# ProPrj___2026-07-14.net
KiCad netlist of a schematic drawn in EasyEDA Pro
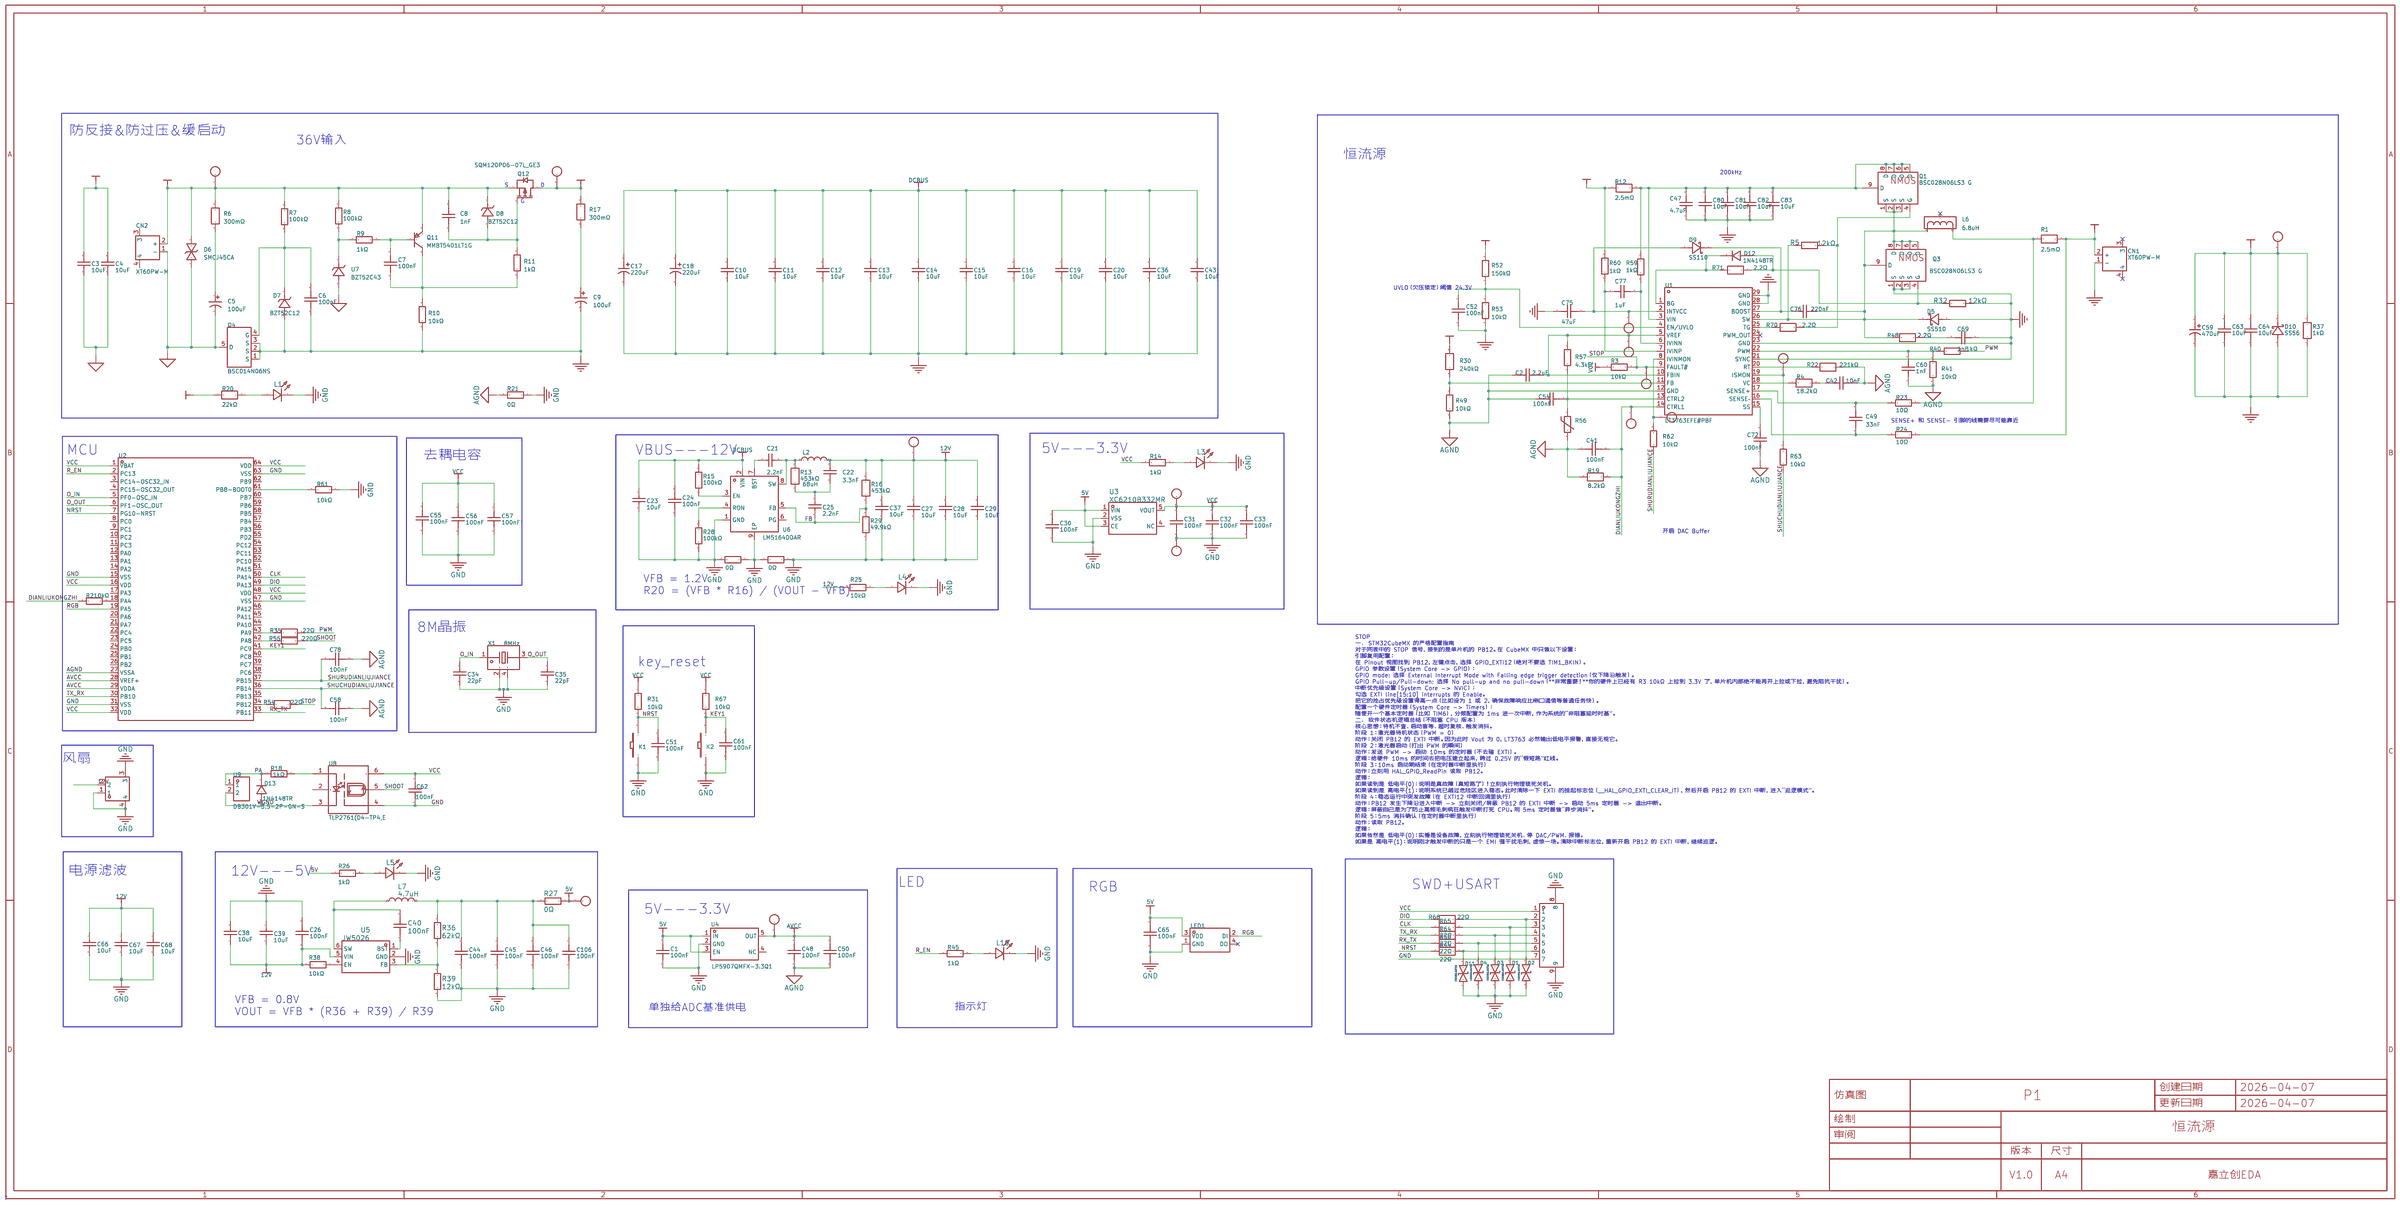
[diagram p0: schematic sheet]

(export (version "E")
  (design (tool "Eeschema 10.0.6"))
  (components
    (comp (ref "C1")
      (value "100nF")
      (description "容值:100nF;精度:±10%;额定电压:50V;温度系数:X7R;")
      (fields
        (field (name "Manufacturer Part") "CC0603KRX7R9BB104")
        (field (name "Manufacturer") "YAGEO(国巨)")
      )
      (libsource (lib "easyedapro") (part "CC0603KRX7R9BB104"))
    )
    (comp (ref "C2")
      (value "2.2uF")
      (footprint "easyedapro:C0603")
      (description "容值:2.2uF;精度:±10%;额定电压:25V;温度系数:X5R;")
      (fields
        (field (name "Manufacturer Part") "CL10A225KA8NNNC")
        (field (name "Manufacturer") "SAMSUNG(三星)")
      )
      (libsource (lib "easyedapro") (part "CL10A225KA8NNNC"))
    )
    (comp (ref "C3")
      (value "10uF")
      (footprint "easyedapro:C1210")
      (description "容值:10uF;精度:±10%;额定电压:50V;温度系数:X7R;")
      (fields
        (field (name "Manufacturer Part") "GRM32ER71H106KA12L")
        (field (name "Manufacturer") "muRata(村田)")
      )
      (libsource (lib "easyedapro") (part "GRM32ER71H106KA12L"))
    )
    (comp (ref "C4")
      (value "10uF")
      (footprint "easyedapro:C1210")
      (description "容值:10uF;精度:±10%;额定电压:50V;温度系数:X7R;")
      (fields
        (field (name "Manufacturer Part") "GRM32ER71H106KA12L")
        (field (name "Manufacturer") "muRata(村田)")
      )
      (libsource (lib "easyedapro") (part "GRM32ER71H106KA12L"))
    )
    (comp (ref "C5")
      (value "100uF")
      (footprint "easyedapro:CAP-TH_BD8.0-P3.50-D0.6-FD")
      (description "容值:100uF;精度:±20%;额定电压:63V;纹波电流:200mA@120Hz;等效串联电阻(ESR):-;")
      (fields (field (name "Manufacturer Part") "RVT63V100M10X10") (field (name "Manufacturer") "JIERR(捷而瑞)"))
      (libsource (lib "easyedapro") (part "ERS1HM101F12OT"))
    )
    (comp (ref "C6")
      (value "100nF")
      (description "容值:100nF;精度:±10%;额定电压:50V;温度系数:X7R;")
      (fields
        (field (name "Manufacturer Part") "CC0603KRX7R9BB104")
        (field (name "Manufacturer") "YAGEO(国巨)")
      )
      (libsource (lib "easyedapro") (part "CC0603KRX7R9BB104"))
    )
    (comp (ref "C7")
      (value "100nF")
      (description "容值:100nF;精度:±10%;额定电压:50V;温度系数:X7R;")
      (fields
        (field (name "Manufacturer Part") "CC0603KRX7R9BB104")
        (field (name "Manufacturer") "YAGEO(国巨)")
      )
      (libsource (lib "easyedapro") (part "CC0603KRX7R9BB104"))
    )
    (comp (ref "C8")
      (value "1nF")
      (footprint "easyedapro:C0805")
      (description "容值:1nF;精度:±10%;额定电压:50V;温度系数:X7R;")
      (fields
        (field (name "Manufacturer Part") "CC0805KRX7R9BB102")
        (field (name "Manufacturer") "YAGEO(国巨)")
      )
      (libsource (lib "easyedapro") (part "CC0805KRX7R9BB102"))
    )
    (comp (ref "C9")
      (value "100uF")
      (footprint "easyedapro:CAP-TH_BD8.0-P3.50-D0.6-FD")
      (description "容值:100uF;精度:±20%;额定电压:63V;纹波电流:200mA@120Hz;等效串联电阻(ESR):-;")
      (fields (field (name "Manufacturer Part") "RVT63V100M10X10") (field (name "Manufacturer") "JIERR(捷而瑞)"))
      (libsource (lib "easyedapro") (part "ERS1HM101F12OT"))
    )
    (comp (ref "C10")
      (value "10uF")
      (footprint "easyedapro:C1210")
      (description "容值:10uF;精度:±10%;额定电压:50V;温度系数:X7R;")
      (fields
        (field (name "Manufacturer Part") "GRM32ER71H106KA12L")
        (field (name "Manufacturer") "muRata(村田)")
      )
      (libsource (lib "easyedapro") (part "GRM32ER71H106KA12L"))
    )
    (comp (ref "C11")
      (value "10uF")
      (footprint "easyedapro:C1210")
      (description "容值:10uF;精度:±10%;额定电压:50V;温度系数:X7R;")
      (fields
        (field (name "Manufacturer Part") "GRM32ER71H106KA12L")
        (field (name "Manufacturer") "muRata(村田)")
      )
      (libsource (lib "easyedapro") (part "GRM32ER71H106KA12L"))
    )
    (comp (ref "C12")
      (value "10uF")
      (footprint "easyedapro:C1210")
      (description "容值:10uF;精度:±10%;额定电压:50V;温度系数:X7R;")
      (fields
        (field (name "Manufacturer Part") "GRM32ER71H106KA12L")
        (field (name "Manufacturer") "muRata(村田)")
      )
      (libsource (lib "easyedapro") (part "GRM32ER71H106KA12L"))
    )
    (comp (ref "C13")
      (value "10uF")
      (footprint "easyedapro:C1210")
      (description "容值:10uF;精度:±10%;额定电压:50V;温度系数:X7R;")
      (fields
        (field (name "Manufacturer Part") "GRM32ER71H106KA12L")
        (field (name "Manufacturer") "muRata(村田)")
      )
      (libsource (lib "easyedapro") (part "GRM32ER71H106KA12L"))
    )
    (comp (ref "C14")
      (value "10uF")
      (footprint "easyedapro:C1210")
      (description "容值:10uF;精度:±10%;额定电压:50V;温度系数:X7R;")
      (fields
        (field (name "Manufacturer Part") "GRM32ER71H106KA12L")
        (field (name "Manufacturer") "muRata(村田)")
      )
      (libsource (lib "easyedapro") (part "GRM32ER71H106KA12L"))
    )
    (comp (ref "C15")
      (value "10uF")
      (footprint "easyedapro:C1210")
      (description "容值:10uF;精度:±10%;额定电压:50V;温度系数:X7R;")
      (fields
        (field (name "Manufacturer Part") "GRM32ER71H106KA12L")
        (field (name "Manufacturer") "muRata(村田)")
      )
      (libsource (lib "easyedapro") (part "GRM32ER71H106KA12L"))
    )
    (comp (ref "C16")
      (value "10uF")
      (footprint "easyedapro:C1210")
      (description "容值:10uF;精度:±10%;额定电压:50V;温度系数:X7R;")
      (fields
        (field (name "Manufacturer Part") "GRM32ER71H106KA12L")
        (field (name "Manufacturer") "muRata(村田)")
      )
      (libsource (lib "easyedapro") (part "GRM32ER71H106KA12L"))
    )
    (comp (ref "C17")
      (value "220uF")
      (footprint "easyedapro:CAP-TH_BD10.0-P5.00-D0.6-FD_2")
      (description "容值:220uF;精度:±20%;额定电压:63V;纹波电流:3.1A@100kHz;等效串联电阻(ESR):18mΩ@100kHz;类型:聚合物;")
      (fields (field (name "Manufacturer Part") "PA63V220M10x15") (field (name "Manufacturer") "JIERR(捷而瑞)"))
      (libsource (lib "easyedapro") (part "PA63V220M10X15"))
    )
    (comp (ref "C18")
      (value "220uF")
      (footprint "easyedapro:CAP-TH_BD10.0-P5.00-D0.6-FD_2")
      (description "容值:220uF;精度:±20%;额定电压:63V;纹波电流:3.1A@100kHz;等效串联电阻(ESR):18mΩ@100kHz;类型:聚合物;")
      (fields (field (name "Manufacturer Part") "PA63V220M10x15") (field (name "Manufacturer") "JIERR(捷而瑞)"))
      (libsource (lib "easyedapro") (part "PA63V220M10X15"))
    )
    (comp (ref "C19")
      (value "10uF")
      (footprint "easyedapro:C1210")
      (description "容值:10uF;精度:±10%;额定电压:50V;温度系数:X7R;")
      (fields
        (field (name "Manufacturer Part") "GRM32ER71H106KA12L")
        (field (name "Manufacturer") "muRata(村田)")
      )
      (libsource (lib "easyedapro") (part "GRM32ER71H106KA12L"))
    )
    (comp (ref "C20")
      (value "10uF")
      (footprint "easyedapro:C1210")
      (description "容值:10uF;精度:±10%;额定电压:50V;温度系数:X7R;")
      (fields
        (field (name "Manufacturer Part") "GRM32ER71H106KA12L")
        (field (name "Manufacturer") "muRata(村田)")
      )
      (libsource (lib "easyedapro") (part "GRM32ER71H106KA12L"))
    )
    (comp (ref "C21")
      (value "2.2nF")
      (footprint "easyedapro:C0805")
      (description "容值:2.2nF;精度:±5%;额定电压:50V;温度系数:C0G;")
      (fields
        (field (name "Manufacturer Part") "CL21C222JBFNNNE")
        (field (name "Manufacturer") "SAMSUNG(三星)")
      )
      (libsource (lib "easyedapro") (part "CL21C222JBFNNNE"))
    )
    (comp (ref "C22")
      (value "3.3nF")
      (footprint "easyedapro:C0603")
      (description "容值:3.3nF;精度:±10%;额定电压:50V;温度系数:X7R;")
      (fields
        (field (name "Manufacturer Part") "CL10B332KB8NNNC")
        (field (name "Manufacturer") "SAMSUNG(三星)")
      )
      (libsource (lib "easyedapro") (part "CL10B332KB8NNNC"))
    )
    (comp (ref "C23")
      (value "10uF")
      (footprint "easyedapro:C1210")
      (description "容值:10uF;精度:±10%;额定电压:50V;温度系数:X7R;")
      (fields
        (field (name "Manufacturer Part") "GRM32ER71H106KA12L")
        (field (name "Manufacturer") "muRata(村田)")
      )
      (libsource (lib "easyedapro") (part "GRM32ER71H106KA12L"))
    )
    (comp (ref "C24")
      (value "100nF")
      (description "容值:100nF;精度:±10%;额定电压:50V;温度系数:X7R;")
      (fields
        (field (name "Manufacturer Part") "CC0603KRX7R9BB104")
        (field (name "Manufacturer") "YAGEO(国巨)")
      )
      (libsource (lib "easyedapro") (part "CC0603KRX7R9BB104"))
    )
    (comp (ref "C25")
      (value "2.2nF")
      (footprint "easyedapro:C0805")
      (description "容值:2.2nF;精度:±5%;额定电压:50V;温度系数:C0G;")
      (fields
        (field (name "Manufacturer Part") "CL21C222JBFNNNE")
        (field (name "Manufacturer") "SAMSUNG(三星)")
      )
      (libsource (lib "easyedapro") (part "CL21C222JBFNNNE"))
    )
    (comp (ref "C26")
      (value "100nF")
      (description "容值:100nF;精度:±10%;额定电压:50V;温度系数:X7R;")
      (fields
        (field (name "Manufacturer Part") "CC0603KRX7R9BB104")
        (field (name "Manufacturer") "YAGEO(国巨)")
      )
      (libsource (lib "easyedapro") (part "CC0603KRX7R9BB104"))
    )
    (comp (ref "C27")
      (value "10uF")
      (footprint "easyedapro:C1210")
      (description "容值:10uF;精度:±10%;额定电压:50V;温度系数:X5R;")
      (fields
        (field (name "Manufacturer Part") "CGA0805X5R106K500MT")
        (field (name "Manufacturer") "HRE(芯声)")
      )
      (libsource (lib "easyedapro") (part "GRM32ER71H106KA12L"))
    )
    (comp (ref "C28")
      (value "10uF")
      (footprint "easyedapro:C1210")
      (description "容值:10uF;精度:±10%;额定电压:50V;温度系数:X5R;")
      (fields
        (field (name "Manufacturer Part") "CGA0805X5R106K500MT")
        (field (name "Manufacturer") "HRE(芯声)")
      )
      (libsource (lib "easyedapro") (part "GRM32ER71H106KA12L"))
    )
    (comp (ref "C29")
      (value "10uF")
      (footprint "easyedapro:C1210")
      (description "容值:10uF;精度:±10%;额定电压:50V;温度系数:X7R;")
      (fields
        (field (name "Manufacturer Part") "GRM32ER71H106KA12L")
        (field (name "Manufacturer") "muRata(村田)")
      )
      (libsource (lib "easyedapro") (part "GRM32ER71H106KA12L"))
    )
    (comp (ref "C30")
      (value "100nF")
      (description "容值:100nF;精度:±10%;额定电压:50V;温度系数:X7R;")
      (fields
        (field (name "Manufacturer Part") "CC0603KRX7R9BB104")
        (field (name "Manufacturer") "YAGEO(国巨)")
      )
      (libsource (lib "easyedapro") (part "CC0603KRX7R9BB104"))
    )
    (comp (ref "C31")
      (value "100nF")
      (description "容值:100nF;精度:±10%;额定电压:50V;温度系数:X7R;")
      (fields
        (field (name "Manufacturer Part") "CC0603KRX7R9BB104")
        (field (name "Manufacturer") "YAGEO(国巨)")
      )
      (libsource (lib "easyedapro") (part "CC0603KRX7R9BB104"))
    )
    (comp (ref "C32")
      (value "100nF")
      (description "容值:100nF;精度:±10%;额定电压:50V;温度系数:X7R;")
      (fields
        (field (name "Manufacturer Part") "CC0603KRX7R9BB104")
        (field (name "Manufacturer") "YAGEO(国巨)")
      )
      (libsource (lib "easyedapro") (part "CC0603KRX7R9BB104"))
    )
    (comp (ref "C33")
      (value "100nF")
      (description "容值:100nF;精度:±10%;额定电压:50V;温度系数:X7R;")
      (fields
        (field (name "Manufacturer Part") "CC0603KRX7R9BB104")
        (field (name "Manufacturer") "YAGEO(国巨)")
      )
      (libsource (lib "easyedapro") (part "CC0603KRX7R9BB104"))
    )
    (comp (ref "C34")
      (value "22pF")
      (footprint "easyedapro:C0603")
      (description "容值:22pF;精度:±5%;额定电压:50V;温度系数:C0G;")
      (fields
        (field (name "Manufacturer Part") "CL10C220JB8NNNC")
        (field (name "Manufacturer") "SAMSUNG(三星)")
      )
      (libsource (lib "easyedapro") (part "CL10C220JB8NNNC"))
    )
    (comp (ref "C35")
      (value "22pF")
      (footprint "easyedapro:C0603")
      (description "容值:22pF;精度:±5%;额定电压:50V;温度系数:C0G;")
      (fields
        (field (name "Manufacturer Part") "CL10C220JB8NNNC")
        (field (name "Manufacturer") "SAMSUNG(三星)")
      )
      (libsource (lib "easyedapro") (part "CL10C220JB8NNNC"))
    )
    (comp (ref "C36")
      (value "10uF")
      (footprint "easyedapro:C1210")
      (description "容值:10uF;精度:±10%;额定电压:50V;温度系数:X7R;")
      (fields
        (field (name "Manufacturer Part") "GRM32ER71H106KA12L")
        (field (name "Manufacturer") "muRata(村田)")
      )
      (libsource (lib "easyedapro") (part "GRM32ER71H106KA12L"))
    )
    (comp (ref "C37")
      (value "10uF")
      (footprint "easyedapro:C1210")
      (description "容值:10uF;精度:±10%;额定电压:50V;温度系数:X5R;")
      (fields
        (field (name "Manufacturer Part") "CGA0805X5R106K500MT")
        (field (name "Manufacturer") "HRE(芯声)")
      )
      (libsource (lib "easyedapro") (part "GRM32ER71H106KA12L"))
    )
    (comp (ref "C38")
      (value "10uF")
      (footprint "easyedapro:C1210")
      (description "容值:10uF;精度:±10%;额定电压:50V;温度系数:X5R;")
      (fields
        (field (name "Manufacturer Part") "CGA0805X5R106K500MT")
        (field (name "Manufacturer") "HRE(芯声)")
      )
      (libsource (lib "easyedapro") (part "GRM32ER71H106KA12L"))
    )
    (comp (ref "C39")
      (value "10uF")
      (footprint "easyedapro:C1210")
      (description "容值:10uF;精度:±10%;额定电压:50V;温度系数:X5R;")
      (fields
        (field (name "Manufacturer Part") "CGA0805X5R106K500MT")
        (field (name "Manufacturer") "HRE(芯声)")
      )
      (libsource (lib "easyedapro") (part "GRM32ER71H106KA12L"))
    )
    (comp (ref "C40")
      (value "100nF")
      (description "容值:100nF;精度:±10%;额定电压:50V;温度系数:X7R;")
      (fields
        (field (name "Manufacturer Part") "CC0603KRX7R9BB104")
        (field (name "Manufacturer") "YAGEO(国巨)")
      )
      (libsource (lib "easyedapro") (part "CC0603KRX7R9BB104"))
    )
    (comp (ref "C41")
      (value "100nF")
      (description "容值:100nF;精度:±10%;额定电压:50V;温度系数:X7R;")
      (fields
        (field (name "Manufacturer Part") "CC0603KRX7R9BB104")
        (field (name "Manufacturer") "YAGEO(国巨)")
      )
      (libsource (lib "easyedapro") (part "CC0603KRX7R9BB104"))
    )
    (comp (ref "C42")
      (value "10nF")
      (footprint "easyedapro:C0603")
      (description "容值:10nF;精度:±5%;额定电压:100V;温度系数:C0G;")
      (fields (field (name "Manufacturer Part") "CGA3E1C0G2A103JT0Y0E") (field (name "Manufacturer") "TDK"))
      (libsource (lib "easyedapro") (part "CGA3E1C0G2A103JT0Y0E"))
    )
    (comp (ref "C43")
      (value "10uF")
      (footprint "easyedapro:C1210")
      (description "容值:10uF;精度:±10%;额定电压:50V;温度系数:X7R;")
      (fields
        (field (name "Manufacturer Part") "GRM32ER71H106KA12L")
        (field (name "Manufacturer") "muRata(村田)")
      )
      (libsource (lib "easyedapro") (part "GRM32ER71H106KA12L"))
    )
    (comp (ref "C44")
      (value "100nF")
      (description "容值:100nF;精度:±10%;额定电压:50V;温度系数:X7R;")
      (fields
        (field (name "Manufacturer Part") "CC0603KRX7R9BB104")
        (field (name "Manufacturer") "YAGEO(国巨)")
      )
      (libsource (lib "easyedapro") (part "CC0603KRX7R9BB104"))
    )
    (comp (ref "C45")
      (value "100nF")
      (description "容值:100nF;精度:±10%;额定电压:50V;温度系数:X7R;")
      (fields
        (field (name "Manufacturer Part") "CC0603KRX7R9BB104")
        (field (name "Manufacturer") "YAGEO(国巨)")
      )
      (libsource (lib "easyedapro") (part "CC0603KRX7R9BB104"))
    )
    (comp (ref "C46")
      (value "100nF")
      (description "容值:100nF;精度:±10%;额定电压:50V;温度系数:X7R;")
      (fields
        (field (name "Manufacturer Part") "CC0603KRX7R9BB104")
        (field (name "Manufacturer") "YAGEO(国巨)")
      )
      (libsource (lib "easyedapro") (part "CC0603KRX7R9BB104"))
    )
    (comp (ref "C47")
      (value "4.7uF")
      (footprint "easyedapro:C1210")
      (description "容值:4.7uF;精度:±10%;额定电压:100V;温度系数:X7R;")
      (fields
        (field (name "Manufacturer Part") "HHV1210R7475K101NSVK")
        (field (name "Manufacturer") "Chinocera(华瓷)")
      )
      (libsource (lib "easyedapro") (part "HHV1210R7475K101NSVK"))
    )
    (comp (ref "C48")
      (value "100nF")
      (description "容值:100nF;精度:±10%;额定电压:50V;温度系数:X7R;")
      (fields
        (field (name "Manufacturer Part") "CC0603KRX7R9BB104")
        (field (name "Manufacturer") "YAGEO(国巨)")
      )
      (libsource (lib "easyedapro") (part "CC0603KRX7R9BB104"))
    )
    (comp (ref "C49")
      (value "33nF")
      (footprint "easyedapro:C1206")
      (description "容值:33nF;精度:±5%;额定电压:100V;温度系数:C0G;")
      (fields
        (field (name "Manufacturer Part") "GRM3195C2A333JA01D")
        (field (name "Manufacturer") "muRata(村田)")
      )
      (libsource (lib "easyedapro") (part "GRM3195C2A333JA01D"))
    )
    (comp (ref "C50")
      (value "100nF")
      (description "容值:100nF;精度:±10%;额定电压:50V;温度系数:X7R;")
      (fields
        (field (name "Manufacturer Part") "CC0603KRX7R9BB104")
        (field (name "Manufacturer") "YAGEO(国巨)")
      )
      (libsource (lib "easyedapro") (part "CC0603KRX7R9BB104"))
    )
    (comp (ref "C51")
      (value "100nF")
      (description "容值:100nF;精度:±10%;额定电压:50V;温度系数:X7R;")
      (fields
        (field (name "Manufacturer Part") "CC0603KRX7R9BB104")
        (field (name "Manufacturer") "YAGEO(国巨)")
      )
      (libsource (lib "easyedapro") (part "CC0603KRX7R9BB104"))
    )
    (comp (ref "C52")
      (value "100nF")
      (description "容值:100nF;精度:±10%;额定电压:50V;温度系数:X7R;")
      (fields
        (field (name "Manufacturer Part") "CC0603KRX7R9BB104")
        (field (name "Manufacturer") "YAGEO(国巨)")
      )
      (libsource (lib "easyedapro") (part "CC0603KRX7R9BB104"))
    )
    (comp (ref "C54")
      (value "100nF")
      (description "容值:100nF;精度:±10%;额定电压:50V;温度系数:X7R;")
      (fields
        (field (name "Manufacturer Part") "CC0603KRX7R9BB104")
        (field (name "Manufacturer") "YAGEO(国巨)")
      )
      (libsource (lib "easyedapro") (part "CC0603KRX7R9BB104"))
    )
    (comp (ref "C55")
      (value "100nF")
      (description "容值:100nF;精度:±10%;额定电压:50V;温度系数:X7R;")
      (fields
        (field (name "Manufacturer Part") "CC0603KRX7R9BB104")
        (field (name "Manufacturer") "YAGEO(国巨)")
      )
      (libsource (lib "easyedapro") (part "CC0603KRX7R9BB104"))
    )
    (comp (ref "C56")
      (value "100nF")
      (description "容值:100nF;精度:±10%;额定电压:50V;温度系数:X7R;")
      (fields
        (field (name "Manufacturer Part") "CC0603KRX7R9BB104")
        (field (name "Manufacturer") "YAGEO(国巨)")
      )
      (libsource (lib "easyedapro") (part "CC0603KRX7R9BB104"))
    )
    (comp (ref "C57")
      (value "100nF")
      (description "容值:100nF;精度:±10%;额定电压:50V;温度系数:X7R;")
      (fields
        (field (name "Manufacturer Part") "CC0603KRX7R9BB104")
        (field (name "Manufacturer") "YAGEO(国巨)")
      )
      (libsource (lib "easyedapro") (part "CC0603KRX7R9BB104"))
    )
    (comp (ref "C58")
      (value "100nF")
      (description "容值:100nF;精度:±10%;额定电压:50V;温度系数:X7R;")
      (fields
        (field (name "Manufacturer Part") "CC0603KRX7R9BB104")
        (field (name "Manufacturer") "YAGEO(国巨)")
      )
      (libsource (lib "easyedapro") (part "CC0603KRX7R9BB104"))
    )
    (comp (ref "C59")
      (value "470uF")
      (footprint "easyedapro:CAP-TH_BD10.0-P5.00-D0.6-FD-A")
      (fields (field (name "Manufacturer Part") "PA63V470M10X17") (field (name "Manufacturer") "JIERR(捷而瑞)"))
      (libsource (lib "easyedapro") (part "PA63V470M10X17"))
    )
    (comp (ref "C60")
      (value "1nF")
      (footprint "easyedapro:C0805")
      (description "容值:1nF;精度:±10%;额定电压:50V;温度系数:X7R;")
      (fields
        (field (name "Manufacturer Part") "CC0805KRX7R9BB102")
        (field (name "Manufacturer") "YAGEO(国巨)")
      )
      (libsource (lib "easyedapro") (part "CC0805KRX7R9BB102"))
    )
    (comp (ref "C61")
      (value "100nF")
      (description "容值:100nF;精度:±10%;额定电压:50V;温度系数:X7R;")
      (fields
        (field (name "Manufacturer Part") "CC0603KRX7R9BB104")
        (field (name "Manufacturer") "YAGEO(国巨)")
      )
      (libsource (lib "easyedapro") (part "CC0603KRX7R9BB104"))
    )
    (comp (ref "C62")
      (value "100nF")
      (description "容值:100nF;精度:±10%;额定电压:50V;温度系数:X7R;")
      (fields
        (field (name "Manufacturer Part") "CC0603KRX7R9BB104")
        (field (name "Manufacturer") "YAGEO(国巨)")
      )
      (libsource (lib "easyedapro") (part "CC0603KRX7R9BB104"))
    )
    (comp (ref "C63")
      (value "10uF")
      (footprint "easyedapro:C1210")
      (description "容值:10uF;精度:±10%;额定电压:100V;温度系数:X7R;")
      (fields (field (name "Manufacturer Part") "FS32X106K101EGG") (field (name "Manufacturer") "PSA(信昌电陶)"))
      (libsource (lib "easyedapro") (part "FS32X106K101EGG"))
    )
    (comp (ref "C64")
      (value "10uF")
      (footprint "easyedapro:C1210")
      (description "容值:10uF;精度:±10%;额定电压:100V;温度系数:X7R;")
      (fields (field (name "Manufacturer Part") "FS32X106K101EGG") (field (name "Manufacturer") "PSA(信昌电陶)"))
      (libsource (lib "easyedapro") (part "FS32X106K101EGG"))
    )
    (comp (ref "C65")
      (value "100nF")
      (description "容值:100nF;精度:±10%;额定电压:50V;温度系数:X7R;")
      (fields
        (field (name "Manufacturer Part") "CC0603KRX7R9BB104")
        (field (name "Manufacturer") "YAGEO(国巨)")
      )
      (libsource (lib "easyedapro") (part "CC0603KRX7R9BB104"))
    )
    (comp (ref "C66")
      (value "10uF")
      (footprint "easyedapro:C1210")
      (description "容值:10uF;精度:±10%;额定电压:50V;温度系数:X5R;")
      (fields
        (field (name "Manufacturer Part") "CGA0805X5R106K500MT")
        (field (name "Manufacturer") "HRE(芯声)")
      )
      (libsource (lib "easyedapro") (part "GRM32ER71H106KA12L"))
    )
    (comp (ref "C67")
      (value "10uF")
      (footprint "easyedapro:C1210")
      (description "容值:10uF;精度:±10%;额定电压:50V;温度系数:X5R;")
      (fields
        (field (name "Manufacturer Part") "CGA0805X5R106K500MT")
        (field (name "Manufacturer") "HRE(芯声)")
      )
      (libsource (lib "easyedapro") (part "GRM32ER71H106KA12L"))
    )
    (comp (ref "C68")
      (value "10uF")
      (footprint "easyedapro:C1210")
      (description "容值:10uF;精度:±10%;额定电压:50V;温度系数:X5R;")
      (fields
        (field (name "Manufacturer Part") "CGA0805X5R106K500MT")
        (field (name "Manufacturer") "HRE(芯声)")
      )
      (libsource (lib "easyedapro") (part "GRM32ER71H106KA12L"))
    )
    (comp (ref "C69")
      (value "1nF")
      (footprint "easyedapro:C1210")
      (description "容值:1nF;精度:±5%;额定电压:2kV;温度系数:C0G;")
      (fields (field (name "Manufacturer Part") "FV32N102J202EFG") (field (name "Manufacturer") "PSA(信昌电陶)"))
      (libsource (lib "easyedapro") (part "FV32N102J202EFG"))
    )
    (comp (ref "C72")
      (value "100nF")
      (description "容值:100nF;精度:±10%;额定电压:50V;温度系数:X7R;")
      (fields
        (field (name "Manufacturer Part") "CC0603KRX7R9BB104")
        (field (name "Manufacturer") "YAGEO(国巨)")
      )
      (libsource (lib "easyedapro") (part "CC0603KRX7R9BB104"))
    )
    (comp (ref "C75")
      (value "47uF")
      (footprint "easyedapro:C1210")
      (description "容值:47uF;精度:±20%;额定电压:25V;温度系数:X5R;")
      (fields
        (field (name "Manufacturer Part") "HGC1210R5476M250NSVK")
        (field (name "Manufacturer") "Chinocera(华瓷)")
      )
      (libsource (lib "easyedapro") (part "HGC1210R5476M250NSVK"))
    )
    (comp (ref "C76")
      (value "220nF")
      (footprint "easyedapro:C0603")
      (description "容值:220nF;精度:±10%;额定电压:25V;温度系数:X7R;")
      (fields
        (field (name "Manufacturer Part") "CL10B224KA8NNNC")
        (field (name "Manufacturer") "SAMSUNG(三星)")
      )
      (libsource (lib "easyedapro") (part "CL10B224KA8NNNC"))
    )
    (comp (ref "C77")
      (value "1uF")
      (footprint "easyedapro:C0805")
      (description "容值:1uF;精度:±10%;额定电压:100V;温度系数:X7R;")
      (fields
        (field (name "Manufacturer Part") "CC0805KKX7R0BB105")
        (field (name "Manufacturer") "YAGEO(国巨)")
      )
      (libsource (lib "easyedapro") (part "CC0805KKX7R0BB105"))
    )
    (comp (ref "C78")
      (value "100nF")
      (description "容值:100nF;精度:±10%;额定电压:50V;温度系数:X7R;")
      (fields
        (field (name "Manufacturer Part") "CC0603KRX7R9BB104")
        (field (name "Manufacturer") "YAGEO(国巨)")
      )
      (libsource (lib "easyedapro") (part "CC0603KRX7R9BB104"))
    )
    (comp (ref "C80")
      (value "10uF")
      (footprint "easyedapro:C1210")
      (description "容值:10uF;精度:±10%;额定电压:100V;温度系数:X7R;")
      (fields (field (name "Manufacturer Part") "FS32X106K101EGG") (field (name "Manufacturer") "PSA(信昌电陶)"))
      (libsource (lib "easyedapro") (part "FS32X106K101EGG"))
    )
    (comp (ref "C81")
      (value "10uF")
      (footprint "easyedapro:C1210")
      (description "容值:10uF;精度:±10%;额定电压:100V;温度系数:X7R;")
      (fields (field (name "Manufacturer Part") "FS32X106K101EGG") (field (name "Manufacturer") "PSA(信昌电陶)"))
      (libsource (lib "easyedapro") (part "FS32X106K101EGG"))
    )
    (comp (ref "C82")
      (value "10uF")
      (footprint "easyedapro:C1210")
      (description "容值:10uF;精度:±10%;额定电压:100V;温度系数:X7R;")
      (fields (field (name "Manufacturer Part") "FS32X106K101EGG") (field (name "Manufacturer") "PSA(信昌电陶)"))
      (libsource (lib "easyedapro") (part "FS32X106K101EGG"))
    )
    (comp (ref "C83")
      (value "10uF")
      (footprint "easyedapro:C1210")
      (description "容值:10uF;精度:±10%;额定电压:100V;温度系数:X7R;")
      (fields (field (name "Manufacturer Part") "FS32X106K101EGG") (field (name "Manufacturer") "PSA(信昌电陶)"))
      (libsource (lib "easyedapro") (part "FS32X106K101EGG"))
    )
    (comp (ref "C106")
      (value "100nF")
      (description "容值:100nF;精度:±10%;额定电压:50V;温度系数:X7R;")
      (fields
        (field (name "Manufacturer Part") "CC0603KRX7R9BB104")
        (field (name "Manufacturer") "YAGEO(国巨)")
      )
      (libsource (lib "easyedapro") (part "CC0603KRX7R9BB104"))
    )
    (comp (ref "CN1")
      (value "XT60PW-M")
      (footprint "easyedapro:CONN-TH_XT60PW-M")
      (description "模型锂电连接器")
      (fields (field (name "Manufacturer") "AMASS(艾迈斯)"))
      (libsource (lib "easyedapro") (part "XT60PW-M"))
    )
    (comp (ref "CN2")
      (value "XT60PW-M")
      (footprint "easyedapro:CONN-TH_XT60PW-M")
      (description "模型锂电连接器")
      (fields (field (name "Manufacturer") "AMASS(艾迈斯)"))
      (libsource (lib "easyedapro") (part "XT60PW-M"))
    )
    (comp (ref "CN3")
      (value "5012")
      (footprint "easyedapro:测试点")
      (fields (field (name "Manufacturer") "Keystone"))
      (libsource (lib "easyedapro") (part "5012"))
    )
    (comp (ref "CN4")
      (value "5012")
      (footprint "easyedapro:测试点")
      (fields (field (name "Manufacturer") "Keystone"))
      (libsource (lib "easyedapro") (part "5012"))
    )
    (comp (ref "CN5")
      (value "5012")
      (footprint "easyedapro:测试点")
      (fields (field (name "Manufacturer") "Keystone"))
      (libsource (lib "easyedapro") (part "5012"))
    )
    (comp (ref "CN6")
      (value "5012")
      (footprint "easyedapro:测试点")
      (fields (field (name "Manufacturer") "Keystone"))
      (libsource (lib "easyedapro") (part "5012"))
    )
    (comp (ref "CN7")
      (value "5012")
      (footprint "easyedapro:测试点")
      (fields (field (name "Manufacturer") "Keystone"))
      (libsource (lib "easyedapro") (part "5012"))
    )
    (comp (ref "CN8")
      (value "5012")
      (footprint "easyedapro:测试点")
      (fields (field (name "Manufacturer") "Keystone"))
      (libsource (lib "easyedapro") (part "5012"))
    )
    (comp (ref "CN9")
      (value "WAFER-GH1.25-7PWB")
      (footprint "easyedapro:CONN-SMD_7P-P1.25_FWF12514-S07B24W5M")
      (fields (field (name "Manufacturer") "XUNPU(讯普)"))
      (libsource (lib "easyedapro") (part "WAFER-GH1.25-7PWB"))
    )
    (comp (ref "CN10")
      (value "2.54-2A-LT")
      (footprint "easyedapro:CONN-SMD_2P-P2.54_XH2.54-2AB")
      (fields (field (name "Manufacturer") "CAX(创都)"))
      (libsource (lib "easyedapro") (part "2.54-2A-LT"))
    )
    (comp (ref "CN11")
      (value "5012")
      (footprint "easyedapro:测试点")
      (fields (field (name "Manufacturer") "Keystone"))
      (libsource (lib "easyedapro") (part "5012"))
    )
    (comp (ref "CN12")
      (value "5012")
      (footprint "easyedapro:测试点")
      (fields (field (name "Manufacturer") "Keystone"))
      (libsource (lib "easyedapro") (part "5012"))
    )
    (comp (ref "CN13")
      (value "5012")
      (footprint "easyedapro:测试点")
      (fields (field (name "Manufacturer") "Keystone"))
      (libsource (lib "easyedapro") (part "5012"))
    )
    (comp (ref "CN14")
      (value "5012")
      (footprint "easyedapro:测试点")
      (fields (field (name "Manufacturer") "Keystone"))
      (libsource (lib "easyedapro") (part "5012"))
    )
    (comp (ref "CN15")
      (value "5012")
      (footprint "easyedapro:测试点")
      (fields (field (name "Manufacturer") "Keystone"))
      (libsource (lib "easyedapro") (part "5012"))
    )
    (comp (ref "CN16")
      (value "5012")
      (footprint "easyedapro:测试点")
      (fields (field (name "Manufacturer") "Keystone"))
      (libsource (lib "easyedapro") (part "5012"))
    )
    (comp (ref "CN17")
      (value "5012")
      (footprint "easyedapro:测试点")
      (fields (field (name "Manufacturer") "Keystone"))
      (libsource (lib "easyedapro") (part "5012"))
    )
    (comp (ref "CN18")
      (value "5012")
      (footprint "easyedapro:测试点")
      (fields (field (name "Manufacturer") "Keystone"))
      (libsource (lib "easyedapro") (part "5012"))
    )
    (comp (ref "D1")
      (value "ESD9B5.0ST5G")
      (description "极性:双向;反向截止电压(Vrwm):5V;钳位电压:15V;峰值脉冲功率(Ppp):-;击穿电压:7.8V;")
      (fields (field (name "Manufacturer") "onsemi(安森美)"))
      (libsource (lib "easyedapro") (part "ESD9B5.0ST5G"))
    )
    (comp (ref "D2")
      (value "ESD9B5.0ST5G")
      (description "极性:双向;反向截止电压(Vrwm):5V;钳位电压:15V;峰值脉冲功率(Ppp):-;击穿电压:7.8V;")
      (fields (field (name "Manufacturer") "onsemi(安森美)"))
      (libsource (lib "easyedapro") (part "ESD9B5.0ST5G"))
    )
    (comp (ref "D3")
      (value "ESD9B5.0ST5G")
      (description "极性:双向;反向截止电压(Vrwm):5V;钳位电压:15V;峰值脉冲功率(Ppp):-;击穿电压:7.8V;")
      (fields (field (name "Manufacturer") "onsemi(安森美)"))
      (libsource (lib "easyedapro") (part "ESD9B5.0ST5G"))
    )
    (comp (ref "D4")
      (value "ESD9B5.0ST5G")
      (description "极性:双向;反向截止电压(Vrwm):5V;钳位电压:15V;峰值脉冲功率(Ppp):-;击穿电压:7.8V;")
      (fields (field (name "Manufacturer") "onsemi(安森美)"))
      (libsource (lib "easyedapro") (part "ESD9B5.0ST5G"))
    )
    (comp (ref "D5")
      (value "SS510")
      (footprint "easyedapro:SMA_L4.3-W2.6-LS5.0-RD")
      (description "二极管配置:独立式;正向压降(Vf):850mV@5A;直流反向耐压(Vr):100V;整流电流:5A;")
      (fields (field (name "Manufacturer") "R+O(宏嘉诚)"))
      (libsource (lib "easyedapro") (part "SS510_C18199171"))
    )
    (comp (ref "D6")
      (value "SMCJ45CA")
      (footprint "easyedapro:SMC_L6.9-W5.9-LS7.9-BI")
      (description "极性:双向;反向截止电压(Vrwm):45V;钳位电压:72.7V;峰值脉冲电流(Ipp):20.6A;峰值脉冲功率(Ppp):1.5kW;击穿电压:55.3V;")
      (fields (field (name "Manufacturer") "R+O(宏嘉诚)"))
      (libsource (lib "easyedapro") (part "SMCJ45CA_C41411750"))
    )
    (comp (ref "D7")
      (value "BZT52C12")
      (footprint "easyedapro:SOD-123_L2.7-W1.6-LS3.7-RD")
      (description "二极管配置:独立式;稳压值(标称值):12V;稳压值(范围):11.4V~12.6V;耗散功率(Pd):350mW;")
      (fields (field (name "Manufacturer") "R+O(宏嘉诚)"))
      (libsource (lib "easyedapro") (part "BZT52C12_C19077410"))
    )
    (comp (ref "D8")
      (value "BZT52C12")
      (footprint "easyedapro:SOD-123_L2.7-W1.6-LS3.7-RD")
      (description "二极管配置:独立式;稳压值(标称值):12V;稳压值(范围):11.4V~12.6V;耗散功率(Pd):350mW;")
      (fields (field (name "Manufacturer") "R+O(宏嘉诚)"))
      (libsource (lib "easyedapro") (part "BZT52C12_C19077410"))
    )
    (comp (ref "D9")
      (value "SS110")
      (footprint "easyedapro:SMA_L4.3-W2.6-LS5.0-RD")
      (description "二极管配置:独立式;正向压降(Vf):850mV@1A;直流反向耐压(Vr):100V;整流电流:1A;")
      (fields (field (name "Manufacturer") "R+O(宏嘉诚)"))
      (libsource (lib "easyedapro") (part "SS110_C18199178"))
    )
    (comp (ref "D10")
      (value "SS56")
      (footprint "easyedapro:SMA_L4.3-W2.6-LS5.0-RD")
      (description "二极管配置:独立式;正向压降(Vf):700mV@5.0A;直流反向耐压(Vr):60V;整流电流:5A;")
      (fields (field (name "Manufacturer") "R+O(宏嘉诚)"))
      (libsource (lib "easyedapro") (part "SS56_C18199169"))
    )
    (comp (ref "D11")
      (value "ESD9B5.0ST5G")
      (description "极性:双向;反向截止电压(Vrwm):5V;钳位电压:15V;峰值脉冲功率(Ppp):-;击穿电压:7.8V;")
      (fields (field (name "Manufacturer") "onsemi(安森美)"))
      (libsource (lib "easyedapro") (part "ESD9B5.0ST5G"))
    )
    (comp (ref "D12")
      (value "1N4148TR")
      (footprint "easyedapro:DO-35_BD2.0-L4.2-P8.20-D0.5-RD")
      (fields (field (name "Manufacturer") "onsemi(安森美)"))
      (libsource (lib "easyedapro") (part "1N4148TR"))
    )
    (comp (ref "D13")
      (value "1N4148TR")
      (footprint "easyedapro:DO-35_BD2.0-L4.2-P8.20-D0.5-RD")
      (description "二极管配置:1个独立式;整流电流:200mA;直流反向耐压(Vr):100V;正向压降(Vf):1V@10mA;反向恢复时间(Trr):4ns;")
      (fields (field (name "Manufacturer") "onsemi(安森美)"))
      (libsource (lib "easyedapro") (part "1N4148TR"))
    )
    (comp (ref "K1")
      (value "TS-KG02S")
      (footprint "easyedapro:SW-SMD_4P-L6.0-W6.0-P4.50-LS8.5")
      (description "电路结构:单刀单掷;触点电流:50mA;额定电压(DC):12V;安装方式:立贴;绝缘电阻:100MΩ;带灯:-;机械寿命:-;")
      (fields (field (name "Manufacturer") "HANBO(汉博)"))
      (libsource (lib "easyedapro") (part "TS-KG02S"))
    )
    (comp (ref "K2")
      (value "TS-KG02S")
      (footprint "easyedapro:SW-SMD_4P-L6.0-W6.0-P4.50-LS8.5")
      (description "电路结构:单刀单掷;触点电流:50mA;额定电压(DC):12V;安装方式:立贴;绝缘电阻:100MΩ;带灯:-;机械寿命:-;")
      (fields (field (name "Manufacturer") "HANBO(汉博)"))
      (libsource (lib "easyedapro") (part "TS-KG02S"))
    )
    (comp (ref "L1")
      (value "NCD0603R1")
      (fields (field (name "Manufacturer") "国星光电"))
      (libsource (lib "easyedapro") (part "LED-0603_R"))
    )
    (comp (ref "L2")
      (value "68uH")
      (footprint "easyedapro:IND-SMD_L7.2-W6.6_GPSR07X0")
      (description "电感值:68uH;精度:±20%;额定电流:1.8A;直流电阻(DCR):315mΩ;")
      (fields (field (name "Manufacturer Part") "CYA0650-68UH") (field (name "Manufacturer") "SHOU HAN(首韩)"))
      (libsource (lib "easyedapro") (part "CYA0650-68UH"))
    )
    (comp (ref "L3")
      (value "NCD0603R1")
      (fields (field (name "Manufacturer") "国星光电"))
      (libsource (lib "easyedapro") (part "LED-0603_R"))
    )
    (comp (ref "L4")
      (value "NCD0603R1")
      (fields (field (name "Manufacturer") "国星光电"))
      (libsource (lib "easyedapro") (part "LED-0603_R"))
    )
    (comp (ref "L5")
      (value "NCD0603R1")
      (fields (field (name "Manufacturer") "国星光电"))
      (libsource (lib "easyedapro") (part "LED-0603_R"))
    )
    (comp (ref "L6")
      (value "6.8uH")
      (footprint "easyedapro:IND-SMD_3P-L28.0-W27.0")
      (description "电感值:6.8uH;精度:±20%;额定电流:30A;饱和电流(Isat):40A;类型:扁平线电感;")
      (fields (field (name "Manufacturer Part") "MTP2915-6R8MC") (field (name "Manufacturer") "COILMX(迈翔科技)"))
      (libsource (lib "easyedapro") (part "MTP2915-6R8MC"))
    )
    (comp (ref "L7")
      (value "4.7uH")
      (description "电感值:4.7uH;精度:±20%;额定电流:1A;")
      (fields
        (field (name "Manufacturer Part") "MPIH252010-4R7M-LF")
        (field (name "Manufacturer") "microgate(麦捷科技)")
      )
      (libsource (lib "easyedapro") (part "2.2uH"))
    )
    (comp (ref "L10")
      (value "NCD0603G1")
      (fields (field (name "Manufacturer") "国星光电"))
      (libsource (lib "easyedapro") (part "LED-0603_R"))
    )
    (comp (ref "LED1")
      (value "XL-3528RGBW-2812B")
      (footprint "easyedapro:LED-SMD_4P-L3.5-W2.8-BR-1")
      (description "3528幻彩雾状   内置驱动IC    WS2812B")
      (fields (field (name "Manufacturer") "XINGLIGHT(成兴光)"))
      (libsource (lib "easyedapro") (part "XL-3528RGBW-WS2812B"))
    )
    (comp (ref "Q1")
      (value "BSC028N06LS3 G")
      (footprint "easyedapro:PG-TDSON-8_L5.9-W5.2-P1.27-LS6.2-BL-EP")
      (fields (field (name "Manufacturer") "Infineon(英飞凌)"))
      (libsource (lib "easyedapro") (part "BSC028N06LS3 G"))
    )
    (comp (ref "Q3")
      (value "BSC028N06LS3 G")
      (footprint "easyedapro:PG-TDSON-8_L5.9-W5.2-P1.27-LS6.2-BL-EP")
      (fields (field (name "Manufacturer") "Infineon(英飞凌)"))
      (libsource (lib "easyedapro") (part "BSC028N06LS3 G"))
    )
    (comp (ref "Q4")
      (value "BSC014N06NS")
      (footprint "easyedapro:POWERVDFN-8_L6.2-W5.2-P1.27-LS6.0-BL")
      (fields (field (name "Manufacturer") "Infineon(英飞凌)"))
      (libsource (lib "easyedapro") (part "BSC014N06NS"))
    )
    (comp (ref "Q11")
      (value "MMBT5401LT1G")
      (footprint "easyedapro:SOT-23-3_L2.9-W1.3-P1.90-LS2.4-BR")
      (description "晶体管类型:PNP;集电极电流(Ic):500mA;集射极击穿电压(Vceo):150V;耗散功率(Pd):300mW;直流电流增益(hFE):60@10mA,5V;")
      (fields (field (name "Manufacturer") "onsemi(安森美)"))
      (libsource (lib "easyedapro") (part "MMBT5401LT1G"))
    )
    (comp (ref "Q12")
      (value "SQM120P06-07L_GE3")
      (footprint "easyedapro:TO-263-2_L10.1-W9.1-P5.08-LS15.2-TL-1")
      (fields (field (name "Manufacturer") "VISHAY(威世)"))
      (libsource (lib "easyedapro") (part "SQM120P06-07L_GE3"))
    )
    (comp (ref "R1")
      (value "2.5mΩ")
      (footprint "easyedapro:R2512")
      (description "阻值:2.5mΩ;精度:±0.5%;功率:3W;温度系数:±100ppm/℃;安装方式:贴片;")
      (fields
        (field (name "Manufacturer Part") "HoCG251232m50D4")
        (field (name "Manufacturer") "Milliohm(毫欧)")
      )
      (libsource (lib "easyedapro") (part "HOCG251232M50D4"))
    )
    (comp (ref "R2")
      (value "10kΩ")
      (footprint "easyedapro:R0805")
      (description "电阻类型:薄膜电阻;阻值:10kΩ;精度:±0.1%;功率:125mW;工作电压:150V;温度系数:±25ppm/℃;")
      (fields (field (name "Manufacturer Part") "RT0805BRD0710KL") (field (name "Manufacturer") "YAGEO(国巨)"))
      (libsource (lib "easyedapro") (part "RT0805BRD0710KL"))
    )
    (comp (ref "R3")
      (value "10kΩ")
      (footprint "easyedapro:R0805")
      (description "电阻类型:薄膜电阻;阻值:10kΩ;精度:±0.1%;功率:125mW;工作电压:150V;温度系数:±25ppm/℃;")
      (fields (field (name "Manufacturer Part") "RT0805BRD0710KL") (field (name "Manufacturer") "YAGEO(国巨)"))
      (libsource (lib "easyedapro") (part "RT0805BRD0710KL"))
    )
    (comp (ref "R4")
      (value "18.2kΩ")
      (footprint "easyedapro:R0603")
      (description "电阻类型:厚膜电阻;阻值:18.2kΩ;精度:±1%;功率:100mW;工作电压:75V;温度系数:±100ppm/℃;")
      (fields (field (name "Manufacturer Part") "FRC0603F1822TS") (field (name "Manufacturer") "FOJAN(富捷)"))
      (libsource (lib "easyedapro") (part "FRC0603F1822TS"))
    )
    (comp (ref "R5")
      (value "12kΩ")
      (description "电阻类型:厚膜电阻;阻值:12kΩ;精度:±1%;功率:100mW;工作电压:75V;温度系数:±100ppm/℃;")
      (fields
        (field (name "Manufacturer Part") "0603WAF1202T5E")
        (field (name "Manufacturer") "UNI-ROYAL(厚声)")
      )
      (libsource (lib "easyedapro") (part "0603WAF1202T5E"))
    )
    (comp (ref "R6")
      (value "300mΩ")
      (footprint "easyedapro:R2512")
      (description "电阻类型:采样电阻;阻值:300mΩ;精度:±1%;功率:3W;安装方式:贴片;")
      (fields
        (field (name "Manufacturer Part") "HoYLR2512-3W-300mR-1%")
        (field (name "Manufacturer") "Milliohm(毫欧)")
      )
      (libsource (lib "easyedapro") (part "HOYLR2512-3W-300MR-1%"))
    )
    (comp (ref "R7")
      (value "100kΩ")
      (footprint "easyedapro:R0805")
      (description "电阻类型:厚膜电阻;阻值:100kΩ;精度:±1%;功率:125mW;工作电压:150V;温度系数:±100ppm/℃;")
      (fields
        (field (name "Manufacturer Part") "0805W8F1003T5E")
        (field (name "Manufacturer") "UNI-ROYAL(厚声)")
      )
      (libsource (lib "easyedapro") (part "0805W8F1003T5E_C149504"))
    )
    (comp (ref "R8")
      (value "100kΩ")
      (footprint "easyedapro:R0805")
      (description "电阻类型:厚膜电阻;阻值:100kΩ;精度:±1%;功率:125mW;工作电压:150V;温度系数:±100ppm/℃;")
      (fields
        (field (name "Manufacturer Part") "0805W8F1003T5E")
        (field (name "Manufacturer") "UNI-ROYAL(厚声)")
      )
      (libsource (lib "easyedapro") (part "0805W8F1003T5E_C149504"))
    )
    (comp (ref "R9")
      (value "1kΩ")
      (footprint "easyedapro:R0805")
      (description "电阻类型:厚膜电阻;阻值:1kΩ;精度:±1%;功率:125mW;最大工作电压:150V;温度系数:±100ppm/℃;")
      (fields
        (field (name "Manufacturer Part") "0805W8F1001T5E")
        (field (name "Manufacturer") "UNI-ROYAL(厚声)")
      )
      (libsource (lib "easyedapro") (part "0805W8F1001T5E"))
    )
    (comp (ref "R10")
      (value "10kΩ")
      (footprint "easyedapro:R0805")
      (description "电阻类型:薄膜电阻;阻值:10kΩ;精度:±0.1%;功率:125mW;工作电压:150V;温度系数:±25ppm/℃;")
      (fields (field (name "Manufacturer Part") "RT0805BRD0710KL") (field (name "Manufacturer") "YAGEO(国巨)"))
      (libsource (lib "easyedapro") (part "RT0805BRD0710KL"))
    )
    (comp (ref "R11")
      (value "1kΩ")
      (footprint "easyedapro:R0805")
      (description "电阻类型:厚膜电阻;阻值:1kΩ;精度:±1%;功率:125mW;最大工作电压:150V;温度系数:±100ppm/℃;")
      (fields
        (field (name "Manufacturer Part") "0805W8F1001T5E")
        (field (name "Manufacturer") "UNI-ROYAL(厚声)")
      )
      (libsource (lib "easyedapro") (part "0805W8F1001T5E"))
    )
    (comp (ref "R12")
      (value "2.5mΩ")
      (footprint "easyedapro:R2512")
      (description "阻值:2.5mΩ;精度:±0.5%;功率:3W;温度系数:±100ppm/℃;安装方式:贴片;")
      (fields
        (field (name "Manufacturer Part") "HoCG251232m50D4")
        (field (name "Manufacturer") "Milliohm(毫欧)")
      )
      (libsource (lib "easyedapro") (part "HOCG251232M50D4"))
    )
    (comp (ref "R13")
      (value "453kΩ")
      (footprint "easyedapro:R0603")
      (description "电阻类型:厚膜电阻;阻值:453kΩ;精度:±1%;功率:100mW;工作电压:75V;温度系数:±100ppm/℃;")
      (fields (field (name "Manufacturer Part") "FRC0603F4533TS") (field (name "Manufacturer") "FOJAN(富捷)"))
      (libsource (lib "easyedapro") (part "FRC0603F4533TS"))
    )
    (comp (ref "R14")
      (value "1kΩ")
      (footprint "easyedapro:R0805")
      (description "电阻类型:厚膜电阻;阻值:1kΩ;精度:±1%;功率:125mW;最大工作电压:150V;温度系数:±100ppm/℃;")
      (fields
        (field (name "Manufacturer Part") "0805W8F1001T5E")
        (field (name "Manufacturer") "UNI-ROYAL(厚声)")
      )
      (libsource (lib "easyedapro") (part "0805W8F1001T5E"))
    )
    (comp (ref "R15")
      (value "100kΩ")
      (footprint "easyedapro:R0805")
      (description "电阻类型:厚膜电阻;阻值:100kΩ;精度:±1%;功率:125mW;工作电压:150V;温度系数:±100ppm/℃;")
      (fields
        (field (name "Manufacturer Part") "0805W8F1003T5E")
        (field (name "Manufacturer") "UNI-ROYAL(厚声)")
      )
      (libsource (lib "easyedapro") (part "0805W8F1003T5E_C149504"))
    )
    (comp (ref "R16")
      (value "453kΩ")
      (footprint "easyedapro:R0603")
      (description "电阻类型:厚膜电阻;阻值:453kΩ;精度:±1%;功率:100mW;工作电压:75V;温度系数:±100ppm/℃;")
      (fields (field (name "Manufacturer Part") "FRC0603F4533TS") (field (name "Manufacturer") "FOJAN(富捷)"))
      (libsource (lib "easyedapro") (part "FRC0603F4533TS"))
    )
    (comp (ref "R17")
      (value "300mΩ")
      (footprint "easyedapro:R2512")
      (description "电阻类型:采样电阻;阻值:300mΩ;精度:±1%;功率:3W;安装方式:贴片;")
      (fields
        (field (name "Manufacturer Part") "HoYLR2512-3W-300mR-1%")
        (field (name "Manufacturer") "Milliohm(毫欧)")
      )
      (libsource (lib "easyedapro") (part "HOYLR2512-3W-300MR-1%"))
    )
    (comp (ref "R18")
      (value "1kΩ")
      (footprint "easyedapro:R0805")
      (description "电阻类型:厚膜电阻;阻值:1kΩ;精度:±1%;功率:125mW;最大工作电压:150V;温度系数:±100ppm/℃;")
      (fields
        (field (name "Manufacturer Part") "0805W8F1001T5E")
        (field (name "Manufacturer") "UNI-ROYAL(厚声)")
      )
      (libsource (lib "easyedapro") (part "0805W8F1001T5E"))
    )
    (comp (ref "R19")
      (value "8.2kΩ")
      (footprint "easyedapro:R0805")
      (description "电阻类型:薄膜电阻;阻值:8.2kΩ;精度:±0.1%;功率:125mW;工作电压:150V;温度系数:±25ppm/℃;")
      (fields
        (field (name "Manufacturer Part") "TC0525B8201T5G")
        (field (name "Manufacturer") "UNI-ROYAL(厚声)")
      )
      (libsource (lib "easyedapro") (part "TC0525B8201T5G"))
    )
    (comp (ref "R20")
      (value "22kΩ")
      (footprint "easyedapro:R0603")
      (description "电阻类型:厚膜电阻;阻值:22kΩ;精度:±1%;功率:100mW;工作电压:75V;温度系数:±100ppm/℃;")
      (fields (field (name "Manufacturer Part") "FRC0603F2202TS") (field (name "Manufacturer") "FOJAN(富捷)"))
      (libsource (lib "easyedapro") (part "FRC0603F2202TS"))
    )
    (comp (ref "R21")
      (value "0Ω")
      (footprint "easyedapro:R0603")
      (description "电阻类型:厚膜电阻;阻值:0Ω;精度:±1%;功率:100mW;工作电压:75V;温度系数:-;")
      (fields
        (field (name "Manufacturer Part") "0603WAF0000T5E")
        (field (name "Manufacturer") "UNI-ROYAL(厚声)")
      )
      (libsource (lib "easyedapro") (part "0603WAF0000T5E"))
    )
    (comp (ref "R22")
      (value "221kΩ")
      (footprint "easyedapro:R0805")
      (description "电阻类型:厚膜电阻;阻值:221kΩ;精度:±1%;功率:125mW;工作电压:150V;温度系数:±100ppm/℃;")
      (fields (field (name "Manufacturer Part") "FRC0805F2213TS") (field (name "Manufacturer") "FOJAN(富捷)"))
      (libsource (lib "easyedapro") (part "FRC0805F2213TS"))
    )
    (comp (ref "R23")
      (value "10Ω")
      (footprint "easyedapro:R0805_NEW")
      (description "电阻类型:厚膜电阻;阻值:10Ω;精度:±1%;功率:125mW;工作电压:150V;温度系数:±200ppm/℃;")
      (fields
        (field (name "Manufacturer Part") "0805W8F100JT5E")
        (field (name "Manufacturer") "UNI-ROYAL(厚声)")
      )
      (libsource (lib "easyedapro") (part "0805W8F100JT5E"))
    )
    (comp (ref "R24")
      (value "10Ω")
      (footprint "easyedapro:R0805_NEW")
      (description "电阻类型:厚膜电阻;阻值:10Ω;精度:±1%;功率:125mW;工作电压:150V;温度系数:±200ppm/℃;")
      (fields
        (field (name "Manufacturer Part") "0805W8F100JT5E")
        (field (name "Manufacturer") "UNI-ROYAL(厚声)")
      )
      (libsource (lib "easyedapro") (part "0805W8F100JT5E"))
    )
    (comp (ref "R25")
      (value "10kΩ")
      (footprint "easyedapro:R0805")
      (description "电阻类型:薄膜电阻;阻值:10kΩ;精度:±0.1%;功率:125mW;工作电压:150V;温度系数:±25ppm/℃;")
      (fields (field (name "Manufacturer Part") "RT0805BRD0710KL") (field (name "Manufacturer") "YAGEO(国巨)"))
      (libsource (lib "easyedapro") (part "RT0805BRD0710KL"))
    )
    (comp (ref "R26")
      (value "1kΩ")
      (footprint "easyedapro:R0805")
      (description "电阻类型:厚膜电阻;阻值:1kΩ;精度:±1%;功率:125mW;最大工作电压:150V;温度系数:±100ppm/℃;")
      (fields
        (field (name "Manufacturer Part") "0805W8F1001T5E")
        (field (name "Manufacturer") "UNI-ROYAL(厚声)")
      )
      (libsource (lib "easyedapro") (part "0805W8F1001T5E"))
    )
    (comp (ref "R27")
      (value "0Ω")
      (footprint "easyedapro:R0603")
      (description "电阻类型:厚膜电阻;阻值:0Ω;精度:±1%;功率:100mW;工作电压:75V;温度系数:-;")
      (fields
        (field (name "Manufacturer Part") "0603WAF0000T5E")
        (field (name "Manufacturer") "UNI-ROYAL(厚声)")
      )
      (libsource (lib "easyedapro") (part "0603WAF0000T5E"))
    )
    (comp (ref "R28")
      (value "100kΩ")
      (footprint "easyedapro:R0805")
      (description "电阻类型:厚膜电阻;阻值:100kΩ;精度:±1%;功率:125mW;工作电压:150V;温度系数:±100ppm/℃;")
      (fields
        (field (name "Manufacturer Part") "0805W8F1003T5E")
        (field (name "Manufacturer") "UNI-ROYAL(厚声)")
      )
      (libsource (lib "easyedapro") (part "0805W8F1003T5E_C149504"))
    )
    (comp (ref "R29")
      (value "49.9kΩ")
      (footprint "easyedapro:R0603")
      (description "电阻类型:厚膜电阻;阻值:49.9kΩ;精度:±1%;功率:100mW;工作电压:75V;温度系数:±100ppm/℃;")
      (fields
        (field (name "Manufacturer Part") "0603WAF4992T5E")
        (field (name "Manufacturer") "UNI-ROYAL(厚声)")
      )
      (libsource (lib "easyedapro") (part "0603WAF4992T5E"))
    )
    (comp (ref "R30")
      (value "240kΩ")
      (footprint "easyedapro:R0603")
      (description "电阻类型:薄膜电阻;阻值:240kΩ;精度:±0.1%;功率:100mW;工作电压:75V;温度系数:±25ppm/℃;")
      (fields (field (name "Manufacturer Part") "RT0603BRD07240KL") (field (name "Manufacturer") "YAGEO(国巨)"))
      (libsource (lib "easyedapro") (part "RT0603BRD07240KL"))
    )
    (comp (ref "R31")
      (value "10kΩ")
      (footprint "easyedapro:R0805")
      (description "电阻类型:薄膜电阻;阻值:10kΩ;精度:±0.1%;功率:125mW;工作电压:150V;温度系数:±25ppm/℃;")
      (fields (field (name "Manufacturer Part") "RT0805BRD0710KL") (field (name "Manufacturer") "YAGEO(国巨)"))
      (libsource (lib "easyedapro") (part "RT0805BRD0710KL"))
    )
    (comp (ref "R32")
      (value "12kΩ")
      (description "电阻类型:厚膜电阻;阻值:12kΩ;精度:±1%;功率:100mW;工作电压:75V;温度系数:±100ppm/℃;")
      (fields
        (field (name "Manufacturer Part") "0603WAF1202T5E")
        (field (name "Manufacturer") "UNI-ROYAL(厚声)")
      )
      (libsource (lib "easyedapro") (part "0603WAF1202T5E"))
    )
    (comp (ref "R33")
      (value "0Ω")
      (footprint "easyedapro:R0603")
      (description "电阻类型:厚膜电阻;阻值:0Ω;精度:±1%;功率:100mW;工作电压:75V;温度系数:-;")
      (fields
        (field (name "Manufacturer Part") "0603WAF0000T5E")
        (field (name "Manufacturer") "UNI-ROYAL(厚声)")
      )
      (libsource (lib "easyedapro") (part "0603WAF0000T5E"))
    )
    (comp (ref "R34")
      (value "0Ω")
      (footprint "easyedapro:R0603")
      (description "电阻类型:厚膜电阻;阻值:0Ω;精度:±1%;功率:100mW;工作电压:75V;温度系数:-;")
      (fields
        (field (name "Manufacturer Part") "0603WAF0000T5E")
        (field (name "Manufacturer") "UNI-ROYAL(厚声)")
      )
      (libsource (lib "easyedapro") (part "0603WAF0000T5E"))
    )
    (comp (ref "R35")
      (value "22Ω")
      (footprint "easyedapro:R0603")
      (description "电阻类型:厚膜电阻;阻值:22Ω;精度:±1%;功率:100mW;工作电压:75V;温度系数:±100ppm/℃;")
      (fields (field (name "Manufacturer Part") "FRC0603F22R0TS") (field (name "Manufacturer") "FOJAN(富捷)"))
      (libsource (lib "easyedapro") (part "FRC0603F22R0TS"))
    )
    (comp (ref "R36")
      (value "62kΩ")
      (footprint "easyedapro:R0805")
      (description "电阻类型:厚膜电阻;阻值:62kΩ;精度:±1%;功率:125mW;工作电压:150V;温度系数:±100ppm/℃;")
      (fields
        (field (name "Manufacturer Part") "0805W8F6202T5E")
        (field (name "Manufacturer") "UNI-ROYAL(厚声)")
      )
      (libsource (lib "easyedapro") (part "0805W8F6202T5E"))
    )
    (comp (ref "R37")
      (value "1kΩ")
      (footprint "easyedapro:R2512")
      (fields (field (name "Manufacturer Part") "FRC2512J102 TS") (field (name "Manufacturer") "FOJAN(富捷)"))
      (libsource (lib "easyedapro") (part "FRC2512J102 TS"))
    )
    (comp (ref "R38")
      (value "10kΩ")
      (footprint "easyedapro:R0805")
      (description "电阻类型:薄膜电阻;阻值:10kΩ;精度:±0.1%;功率:125mW;工作电压:150V;温度系数:±25ppm/℃;")
      (fields (field (name "Manufacturer Part") "RT0805BRD0710KL") (field (name "Manufacturer") "YAGEO(国巨)"))
      (libsource (lib "easyedapro") (part "RT0805BRD0710KL"))
    )
    (comp (ref "R39")
      (value "12kΩ")
      (description "电阻类型:厚膜电阻;阻值:12kΩ;精度:±1%;功率:100mW;工作电压:75V;温度系数:±100ppm/℃;")
      (fields
        (field (name "Manufacturer Part") "0603WAF1202T5E")
        (field (name "Manufacturer") "UNI-ROYAL(厚声)")
      )
      (libsource (lib "easyedapro") (part "0603WAF1202T5E"))
    )
    (comp (ref "R40")
      (value "1kΩ")
      (footprint "easyedapro:R0805")
      (description "电阻类型:厚膜电阻;阻值:1kΩ;精度:±1%;功率:125mW;最大工作电压:150V;温度系数:±100ppm/℃;")
      (fields
        (field (name "Manufacturer Part") "0805W8F1001T5E")
        (field (name "Manufacturer") "UNI-ROYAL(厚声)")
      )
      (libsource (lib "easyedapro") (part "0805W8F1001T5E"))
    )
    (comp (ref "R41")
      (value "10kΩ")
      (footprint "easyedapro:R0805")
      (description "电阻类型:薄膜电阻;阻值:10kΩ;精度:±0.1%;功率:125mW;工作电压:150V;温度系数:±25ppm/℃;")
      (fields (field (name "Manufacturer Part") "RT0805BRD0710KL") (field (name "Manufacturer") "YAGEO(国巨)"))
      (libsource (lib "easyedapro") (part "RT0805BRD0710KL"))
    )
    (comp (ref "R44")
      (value "22Ω")
      (footprint "easyedapro:R0603")
      (description "电阻类型:厚膜电阻;阻值:22Ω;精度:±1%;功率:100mW;工作电压:75V;温度系数:±100ppm/℃;")
      (fields (field (name "Manufacturer Part") "FRC0603F22R0TS") (field (name "Manufacturer") "FOJAN(富捷)"))
      (libsource (lib "easyedapro") (part "FRC0603F22R0TS"))
    )
    (comp (ref "R45")
      (value "1kΩ")
      (footprint "easyedapro:R0805")
      (description "电阻类型:厚膜电阻;阻值:1kΩ;精度:±1%;功率:125mW;最大工作电压:150V;温度系数:±100ppm/℃;")
      (fields
        (field (name "Manufacturer Part") "0805W8F1001T5E")
        (field (name "Manufacturer") "UNI-ROYAL(厚声)")
      )
      (libsource (lib "easyedapro") (part "0805W8F1001T5E"))
    )
    (comp (ref "R48")
      (value "2.2Ω")
      (footprint "easyedapro:R2010")
      (description "电阻类型:厚膜电阻;阻值:2.2Ω;精度:±5%;功率:1.5W;工作电压:400V;温度系数:±400ppm/℃;")
      (fields
        (field (name "Manufacturer Part") "AS101AJ022JT4E")
        (field (name "Manufacturer") "UNI-ROYAL(厚声)")
      )
      (libsource (lib "easyedapro") (part "AS101AJ022JT4E"))
    )
    (comp (ref "R49")
      (value "10kΩ")
      (footprint "easyedapro:R0805")
      (description "电阻类型:薄膜电阻;阻值:10kΩ;精度:±0.1%;功率:125mW;工作电压:150V;温度系数:±25ppm/℃;")
      (fields (field (name "Manufacturer Part") "RT0805BRD0710KL") (field (name "Manufacturer") "YAGEO(国巨)"))
      (libsource (lib "easyedapro") (part "RT0805BRD0710KL"))
    )
    (comp (ref "R50")
      (value "22Ω")
      (footprint "easyedapro:R0603")
      (description "电阻类型:厚膜电阻;阻值:22Ω;精度:±1%;功率:100mW;工作电压:75V;温度系数:±100ppm/℃;")
      (fields (field (name "Manufacturer Part") "FRC0603F22R0TS") (field (name "Manufacturer") "FOJAN(富捷)"))
      (libsource (lib "easyedapro") (part "FRC0603F22R0TS"))
    )
    (comp (ref "R52")
      (value "150kΩ")
      (footprint "easyedapro:R0805")
      (description "电阻类型:薄膜电阻;阻值:150kΩ;精度:±0.1%;功率:125mW;工作电压:150V;温度系数:±25ppm/℃;")
      (fields (field (name "Manufacturer Part") "RT0805BRD07150KL") (field (name "Manufacturer") "YAGEO(国巨)"))
      (libsource (lib "easyedapro") (part "RT0805BRD07150KL"))
    )
    (comp (ref "R53")
      (value "10kΩ")
      (footprint "easyedapro:R0805")
      (description "电阻类型:薄膜电阻;阻值:10kΩ;精度:±0.1%;功率:125mW;工作电压:150V;温度系数:±25ppm/℃;")
      (fields (field (name "Manufacturer Part") "RT0805BRD0710KL") (field (name "Manufacturer") "YAGEO(国巨)"))
      (libsource (lib "easyedapro") (part "RT0805BRD0710KL"))
    )
    (comp (ref "R54")
      (value "22Ω")
      (footprint "easyedapro:R0603")
      (description "电阻类型:厚膜电阻;阻值:22Ω;精度:±1%;功率:100mW;工作电压:75V;温度系数:±100ppm/℃;")
      (fields (field (name "Manufacturer Part") "FRC0603F22R0TS") (field (name "Manufacturer") "FOJAN(富捷)"))
      (libsource (lib "easyedapro") (part "FRC0603F22R0TS"))
    )
    (comp (ref "R55")
      (value "220Ω")
      (footprint "easyedapro:R0603")
      (description "电阻类型:厚膜电阻;阻值:220Ω;精度:±1%;功率:100mW;最大工作电压:75V;温度系数:±100ppm/℃;")
      (fields
        (field (name "Manufacturer Part") "0603WAF2200T5E")
        (field (name "Manufacturer") "UNI-ROYAL(厚声)")
      )
      (libsource (lib "easyedapro") (part "0603WAF2200T5E"))
    )
    (comp (ref "R56")
      (value "HNTC0603-104F3950FB")
      (footprint "easyedapro:R0603")
      (description "功率:100mW;阻值:100kΩ;电阻精度:±1%;B值精度:±1%;B值(25℃/50℃):3950K;最大稳态电流(25℃):100uA;")
      (fields (field (name "Manufacturer") "R+O(宏嘉诚)"))
      (libsource (lib "easyedapro") (part "HNTC0603-104F3950FB"))
    )
    (comp (ref "R57")
      (value "4.3kΩ")
      (footprint "easyedapro:R0603")
      (description "电阻类型:薄膜电阻;阻值:4.3kΩ;精度:±0.1%;功率:100mW;工作电压:50V;温度系数:±25ppm/℃;")
      (fields (field (name "Manufacturer Part") "TD03G4301BT") (field (name "Manufacturer") "FH(风华)"))
      (libsource (lib "easyedapro") (part "TD03G4301BT"))
    )
    (comp (ref "R59")
      (value "1kΩ")
      (footprint "easyedapro:R0805")
      (description "电阻类型:厚膜电阻;阻值:1kΩ;精度:±1%;功率:125mW;最大工作电压:150V;温度系数:±100ppm/℃;")
      (fields
        (field (name "Manufacturer Part") "0805W8F1001T5E")
        (field (name "Manufacturer") "UNI-ROYAL(厚声)")
      )
      (libsource (lib "easyedapro") (part "0805W8F1001T5E"))
    )
    (comp (ref "R60")
      (value "1kΩ")
      (footprint "easyedapro:R0805")
      (description "电阻类型:厚膜电阻;阻值:1kΩ;精度:±1%;功率:125mW;最大工作电压:150V;温度系数:±100ppm/℃;")
      (fields
        (field (name "Manufacturer Part") "0805W8F1001T5E")
        (field (name "Manufacturer") "UNI-ROYAL(厚声)")
      )
      (libsource (lib "easyedapro") (part "0805W8F1001T5E"))
    )
    (comp (ref "R61")
      (value "10kΩ")
      (footprint "easyedapro:R0805")
      (description "电阻类型:薄膜电阻;阻值:10kΩ;精度:±0.1%;功率:125mW;工作电压:150V;温度系数:±25ppm/℃;")
      (fields (field (name "Manufacturer Part") "RT0805BRD0710KL") (field (name "Manufacturer") "YAGEO(国巨)"))
      (libsource (lib "easyedapro") (part "RT0805BRD0710KL"))
    )
    (comp (ref "R62")
      (value "10kΩ")
      (footprint "easyedapro:R0805")
      (description "电阻类型:薄膜电阻;阻值:10kΩ;精度:±0.1%;功率:125mW;工作电压:150V;温度系数:±25ppm/℃;")
      (fields (field (name "Manufacturer Part") "RT0805BRD0710KL") (field (name "Manufacturer") "YAGEO(国巨)"))
      (libsource (lib "easyedapro") (part "RT0805BRD0710KL"))
    )
    (comp (ref "R63")
      (value "10kΩ")
      (footprint "easyedapro:R0805")
      (description "电阻类型:薄膜电阻;阻值:10kΩ;精度:±0.1%;功率:125mW;工作电压:150V;温度系数:±25ppm/℃;")
      (fields (field (name "Manufacturer Part") "RT0805BRD0710KL") (field (name "Manufacturer") "YAGEO(国巨)"))
      (libsource (lib "easyedapro") (part "RT0805BRD0710KL"))
    )
    (comp (ref "R64")
      (value "22Ω")
      (footprint "easyedapro:R0603")
      (description "电阻类型:厚膜电阻;阻值:22Ω;精度:±1%;功率:100mW;工作电压:75V;温度系数:±100ppm/℃;")
      (fields (field (name "Manufacturer Part") "FRC0603F22R0TS") (field (name "Manufacturer") "FOJAN(富捷)"))
      (libsource (lib "easyedapro") (part "FRC0603F22R0TS"))
    )
    (comp (ref "R65")
      (value "22Ω")
      (footprint "easyedapro:R0603")
      (description "电阻类型:厚膜电阻;阻值:22Ω;精度:±1%;功率:100mW;工作电压:75V;温度系数:±100ppm/℃;")
      (fields (field (name "Manufacturer Part") "FRC0603F22R0TS") (field (name "Manufacturer") "FOJAN(富捷)"))
      (libsource (lib "easyedapro") (part "FRC0603F22R0TS"))
    )
    (comp (ref "R66")
      (value "22Ω")
      (footprint "easyedapro:R0603")
      (description "电阻类型:厚膜电阻;阻值:22Ω;精度:±1%;功率:100mW;工作电压:75V;温度系数:±100ppm/℃;")
      (fields (field (name "Manufacturer Part") "FRC0603F22R0TS") (field (name "Manufacturer") "FOJAN(富捷)"))
      (libsource (lib "easyedapro") (part "FRC0603F22R0TS"))
    )
    (comp (ref "R67")
      (value "10kΩ")
      (footprint "easyedapro:R0805")
      (description "电阻类型:薄膜电阻;阻值:10kΩ;精度:±0.1%;功率:125mW;工作电压:150V;温度系数:±25ppm/℃;")
      (fields (field (name "Manufacturer Part") "RT0805BRD0710KL") (field (name "Manufacturer") "YAGEO(国巨)"))
      (libsource (lib "easyedapro") (part "RT0805BRD0710KL"))
    )
    (comp (ref "R70")
      (value "2.2Ω")
      (footprint "easyedapro:R2010")
      (description "电阻类型:厚膜电阻;阻值:2.2Ω;精度:±5%;功率:1.5W;工作电压:400V;温度系数:±400ppm/℃;")
      (fields
        (field (name "Manufacturer Part") "AS101AJ022JT4E")
        (field (name "Manufacturer") "UNI-ROYAL(厚声)")
      )
      (libsource (lib "easyedapro") (part "AS101AJ022JT4E"))
    )
    (comp (ref "R71")
      (value "2.2Ω")
      (footprint "easyedapro:R2010")
      (description "电阻类型:厚膜电阻;阻值:2.2Ω;精度:±5%;功率:1.5W;工作电压:400V;温度系数:±400ppm/℃;")
      (fields
        (field (name "Manufacturer Part") "AS101AJ022JT4E")
        (field (name "Manufacturer") "UNI-ROYAL(厚声)")
      )
      (libsource (lib "easyedapro") (part "AS101AJ022JT4E"))
    )
    (comp (ref "U1")
      (value "LT3763EFE#PBF")
      (footprint "easyedapro:TSSOP-28_L9.7-W4.4-P0.65-LS6.4-BL-EP-1")
      (description "类型:DC-DC控制器;工作电压(DC):6V~60V;开关频率:200kHz~1MHz;通道数:1;输出电压:55V;输出电流:20A;调光:PWM;拓扑结构:降压;")
      (fields (field (name "Manufacturer") "ADI(亚德诺)"))
      (libsource (lib "easyedapro") (part "LT3763EFE#PBF"))
    )
    (comp (ref "U2")
      (value "STM32G431RBT6")
      (footprint "easyedapro:LQFP-64_L10.0-W10.0-P0.50-LS12.0-BL")
      (fields (field (name "Manufacturer") "ST(意法半导体)"))
      (libsource (lib "easyedapro") (part "STM32G431RBT6"))
    )
    (comp (ref "U3")
      (value "XC6210B332MR")
      (description "输出类型:固定;工作电压:6V;输出电压:3.3V;输出电流:900mA;电源纹波抑制比(PSRR):60dB@(1kHz);输出极性:正极;")
      (fields (field (name "Manufacturer") "TOREX(特瑞仕)"))
      (libsource (lib "easyedapro") (part "XC6210B332MR"))
    )
    (comp (ref "U4")
      (value "LP5907QMFX-3.3Q1")
      (description "输出类型:固定;输出极性:正;最大输入电压:5.5V;输出电压:3.3V;输出电流:250mA;电源纹波抑制比(PSRR):90dB;")
      (fields (field (name "Manufacturer") "TI(德州仪器)"))
      (libsource (lib "easyedapro") (part "LP5907QMFX-3.3Q1"))
    )
    (comp (ref "U5")
      (value "JW5026")
      (footprint "easyedapro:SOT-23-6_L2.9-W1.6-P0.95-LS2.8-BR")
      (description "功能类型:降压型;工作电压:4.7V~40V;输出电压:800mV~37V;输出电流:1A;输出类型:可调;")
      (fields (field (name "Manufacturer") "Joulwatt(杰华特)"))
      (libsource (lib "easyedapro") (part "TD1466"))
    )
    (comp (ref "U6")
      (value "LM5164DDAR")
      (footprint "easyedapro:SO-8_L4.9-W3.9-P1.27-LS6.0-BL-EP")
      (description "功能类型:降压型;工作电压:6V~100V;输出电压:-;输出电流:1A;输出类型:可调;")
      (fields (field (name "Manufacturer") "TI(德州仪器)"))
      (libsource (lib "easyedapro") (part "LM5164DDAR"))
    )
    (comp (ref "U7")
      (value "BZT52C43")
      (footprint "easyedapro:SOD-123_L2.7-W1.6-LS3.7-RD")
      (description "二极管配置:独立式;稳压值(标称值):43V;稳压值(范围):40.85V~45.15V;耗散功率(Pd):350mW;")
      (fields (field (name "Manufacturer") "R+O(宏嘉诚)"))
      (libsource (lib "easyedapro") (part "BZT52C43_C22395571"))
    )
    (comp (ref "U8")
      (value "TLP2761(D4-TP4,E")
      (footprint "easyedapro:SOP-6_L7.5-W3.8-P1.27-LS11.1-BL")
      (fields (field (name "Manufacturer") "TOSHIBA(东芝)"))
      (libsource (lib "easyedapro") (part "TLP2761(D4-TP4,E(T"))
    )
    (comp (ref "U9")
      (value "DB301V-3.5-2P-GN-S")
      (footprint "easyedapro:CONN-TH_DB301V-3.5-2P-GN")
      (fields (field (name "Manufacturer") "DORABO(地博电气)"))
      (libsource (lib "easyedapro") (part "DB301V-3.5-2P-GN"))
    )
    (comp (ref "X1")
      (value "8MHz")
      (description "频率:8MHz;负载电容:20pF;频率公差:±10ppm;")
      (fields (field (name "Manufacturer Part") "X32258MSB4SI") (field (name "Manufacturer") "YXC(扬兴晶振)"))
      (libsource (lib "easyedapro") (part "X32258MSB4SI"))
    )
  )
  (nets
    (net (code "1") (name "/CLK") (class "Default")
      (node (ref "R65") (pin "1") (pinfunction "1_1") (pintype "unspecified"))
      (node (ref "U2") (pin "50") (pinfunction "PA14_50") (pintype "input"))
    )
    (net (code "2") (name "/DIANLIUKONGZHI") (class "Default")
      (node (ref "C41") (pin "2") (pinfunction "2_2") (pintype "unspecified"))
      (node (ref "CN13") (pin "1") (pinfunction "1_1") (pintype "input"))
      (node (ref "R19") (pin "1") (pinfunction "1_1") (pintype "unspecified"))
      (node (ref "R2") (pin "2") (pinfunction "2_2") (pintype "input"))
      (node (ref "U1") (pin "14") (pinfunction "CTRL1_14") (pintype "unspecified"))
    )
    (net (code "3") (name "/DIO") (class "Default")
      (node (ref "R66") (pin "1") (pinfunction "1_1") (pintype "unspecified"))
      (node (ref "U2") (pin "49") (pinfunction "PA13_49") (pintype "input"))
    )
    (net (code "4") (name "/FB") (class "Default")
      (node (ref "C25") (pin "2") (pinfunction "2_2") (pintype "input"))
      (node (ref "R16") (pin "1") (pinfunction "1_1") (pintype "unspecified"))
      (node (ref "R29") (pin "2") (pinfunction "2_2") (pintype "input"))
      (node (ref "U6") (pin "5") (pinfunction "FB_5") (pintype "input"))
    )
    (net (code "5") (name "/KEY1") (class "Default")
      (node (ref "C61") (pin "1") (pinfunction "1_1") (pintype "unspecified"))
      (node (ref "K2") (pin "2") (pinfunction "2_2") (pintype "input"))
      (node (ref "R67") (pin "2") (pinfunction "2_2") (pintype "input"))
      (node (ref "U2") (pin "41") (pinfunction "PC9_41") (pintype "input"))
    )
    (net (code "6") (name "/NRST") (class "Default")
      (node (ref "C51") (pin "1") (pinfunction "1_1") (pintype "unspecified"))
      (node (ref "K1") (pin "2") (pinfunction "2_2") (pintype "input"))
      (node (ref "R31") (pin "2") (pinfunction "2_2") (pintype "input"))
      (node (ref "R44") (pin "1") (pinfunction "1_1") (pintype "unspecified"))
      (node (ref "U2") (pin "7") (pinfunction "PG10-NRST_7") (pintype "input"))
    )
    (net (code "7") (name "/O_IN") (class "Default")
      (node (ref "C34") (pin "1") (pinfunction "1_1") (pintype "input"))
      (node (ref "U2") (pin "5") (pinfunction "PF0-OSC_IN_5") (pintype "input"))
      (node (ref "X1") (pin "1") (pinfunction "1_1") (pintype "input"))
    )
    (net (code "8") (name "/O_OUT") (class "Default")
      (node (ref "C35") (pin "1") (pinfunction "1_1") (pintype "input"))
      (node (ref "U2") (pin "6") (pinfunction "PF1-OSC_OUT_6") (pintype "input"))
      (node (ref "X1") (pin "3") (pinfunction "3_3") (pintype "input"))
    )
    (net (code "9") (name "/PA") (class "Default")
      (node (ref "D13") (pin "1") (pinfunction "C_1") (pintype "unspecified"))
      (node (ref "R18") (pin "1") (pinfunction "1_1") (pintype "input"))
      (node (ref "U9") (pin "1") (pinfunction "1_1") (pintype "unspecified"))
    )
    (net (code "10") (name "/PWM") (class "Default")
      (node (ref "R35") (pin "2") (pinfunction "2_2") (pintype "unspecified"))
      (node (ref "R40") (pin "1") (pinfunction "1_1") (pintype "input"))
    )
    (net (code "11") (name "/RGB") (class "Default")
      (node (ref "LED1") (pin "2") (pinfunction "DI_2") (pintype "input"))
      (node (ref "U2") (pin "19") (pinfunction "PA5_19") (pintype "input"))
    )
    (net (code "12") (name "/RX_TX") (class "Default")
      (node (ref "R50") (pin "1") (pinfunction "1_1") (pintype "unspecified"))
      (node (ref "U2") (pin "33") (pinfunction "PB11_33") (pintype "input"))
    )
    (net (code "13") (name "/R_EN") (class "Default")
      (node (ref "R45") (pin "1") (pinfunction "1_1") (pintype "input"))
      (node (ref "U2") (pin "2") (pinfunction "PC13_2") (pintype "input"))
    )
    (net (code "14") (name "/SHOOT") (class "Default")
      (node (ref "R55") (pin "2") (pinfunction "2_2") (pintype "input"))
      (node (ref "U8") (pin "5") (pinfunction "VO(Output)_5") (pintype "unspecified"))
    )
    (net (code "15") (name "/SHUCHUDIANLIUJIANCE") (class "Default")
      (node (ref "C58") (pin "2") (pinfunction "2_2") (pintype "unspecified"))
      (node (ref "R63") (pin "1") (pinfunction "1_1") (pintype "input"))
      (node (ref "U2") (pin "36") (pinfunction "PB14_36") (pintype "input"))
    )
    (net (code "16") (name "/SHURUDIANLIUJIANCE") (class "Default")
      (node (ref "C78") (pin "2") (pinfunction "2_2") (pintype "unspecified"))
      (node (ref "R62") (pin "1") (pinfunction "1_1") (pintype "input"))
      (node (ref "U2") (pin "37") (pinfunction "PB15_37") (pintype "input"))
    )
    (net (code "17") (name "/STOP") (class "Default")
      (node (ref "CN18") (pin "1") (pinfunction "1_1") (pintype "input"))
      (node (ref "R3") (pin "1") (pinfunction "1_1") (pintype "input"))
      (node (ref "R54") (pin "2") (pinfunction "2_2") (pintype "unspecified"))
      (node (ref "U1") (pin "9") (pinfunction "FAULT#_9") (pintype "unspecified"))
    )
    (net (code "18") (name "/TX_RX") (class "Default")
      (node (ref "R64") (pin "1") (pinfunction "1_1") (pintype "unspecified"))
      (node (ref "U2") (pin "30") (pinfunction "PB10_30") (pintype "input"))
    )
    (net (code "19") (name "/WGND") (class "Default")
      (node (ref "D13") (pin "2") (pinfunction "A_2") (pintype "unspecified"))
      (node (ref "U8") (pin "3") (pinfunction "Cathode_3") (pintype "unspecified"))
      (node (ref "U9") (pin "2") (pinfunction "2_2") (pintype "unspecified"))
    )
    (net (code "20") (name "5V") (class "Default")
      (node (ref "C1") (pin "1") (pinfunction "1_1") (pintype "unspecified"))
      (node (ref "C30") (pin "1") (pinfunction "1_1") (pintype "unspecified"))
      (node (ref "C65") (pin "1") (pinfunction "1_1") (pintype "unspecified"))
      (node (ref "CN7") (pin "1") (pinfunction "1_1") (pintype "input"))
      (node (ref "LED1") (pin "3") (pinfunction "VDD_3") (pintype "input"))
      (node (ref "R26") (pin "1") (pinfunction "1_1") (pintype "input"))
      (node (ref "R27") (pin "2") (pinfunction "2_2") (pintype "input"))
      (node (ref "U3") (pin "1") (pinfunction "VIN_1") (pintype "input"))
      (node (ref "U3") (pin "3") (pinfunction "CE_3") (pintype "input"))
      (node (ref "U4") (pin "1") (pinfunction "IN_1") (pintype "input"))
      (node (ref "U4") (pin "3") (pinfunction "EN_3") (pintype "input"))
    )
    (net (code "21") (name "12V") (class "Default")
      (node (ref "C22") (pin "2") (pinfunction "2_2") (pintype "input"))
      (node (ref "C26") (pin "2") (pinfunction "2_2") (pintype "unspecified"))
      (node (ref "C27") (pin "1") (pinfunction "1_1") (pintype "input"))
      (node (ref "C28") (pin "1") (pinfunction "1_1") (pintype "input"))
      (node (ref "C29") (pin "1") (pinfunction "1_1") (pintype "input"))
      (node (ref "C37") (pin "2") (pinfunction "2_2") (pintype "input"))
      (node (ref "C38") (pin "1") (pinfunction "1_1") (pintype "input"))
      (node (ref "C39") (pin "2") (pinfunction "2_2") (pintype "input"))
      (node (ref "C66") (pin "1") (pinfunction "1_1") (pintype "input"))
      (node (ref "C67") (pin "1") (pinfunction "1_1") (pintype "input"))
      (node (ref "C68") (pin "1") (pinfunction "1_1") (pintype "input"))
      (node (ref "CN10") (pin "2") (pinfunction "2_2") (pintype "unspecified"))
      (node (ref "CN11") (pin "1") (pinfunction "1_1") (pintype "input"))
      (node (ref "L2") (pin "2") (pinfunction "2_2") (pintype "unspecified"))
      (node (ref "R16") (pin "2") (pinfunction "2_2") (pintype "unspecified"))
      (node (ref "R25") (pin "1") (pinfunction "1_1") (pintype "input"))
      (node (ref "R38") (pin "1") (pinfunction "1_1") (pintype "input"))
      (node (ref "U5") (pin "5") (pinfunction "VIN_5") (pintype "input"))
    )
    (net (code "22") (name "AGND") (class "Default")
      (node (ref "C2") (pin "2") (pinfunction "2_2") (pintype "unspecified"))
      (node (ref "C41") (pin "1") (pinfunction "1_1") (pintype "unspecified"))
      (node (ref "C42") (pin "2") (pinfunction "2_2") (pintype "unspecified"))
      (node (ref "C48") (pin "2") (pinfunction "2_2") (pintype "unspecified"))
      (node (ref "C50") (pin "2") (pinfunction "2_2") (pintype "unspecified"))
      (node (ref "C54") (pin "1") (pinfunction "1_1") (pintype "unspecified"))
      (node (ref "C58") (pin "1") (pinfunction "1_1") (pintype "unspecified"))
      (node (ref "C60") (pin "1") (pinfunction "1_1") (pintype "unspecified"))
      (node (ref "C72") (pin "1") (pinfunction "1_1") (pintype "unspecified"))
      (node (ref "C78") (pin "1") (pinfunction "1_1") (pintype "unspecified"))
      (node (ref "R19") (pin "2") (pinfunction "2_2") (pintype "unspecified"))
      (node (ref "R21") (pin "2") (pinfunction "2_2") (pintype "input"))
      (node (ref "R22") (pin "1") (pinfunction "1_1") (pintype "unspecified"))
      (node (ref "R41") (pin "2") (pinfunction "2_2") (pintype "input"))
      (node (ref "R49") (pin "2") (pinfunction "2_2") (pintype "input"))
      (node (ref "R56") (pin "2") (pinfunction "2_2") (pintype "unspecified"))
      (node (ref "U1") (pin "12") (pinfunction "GND_12") (pintype "unspecified"))
      (node (ref "U2") (pin "27") (pinfunction "VSSA_27") (pintype "input"))
    )
    (net (code "23") (name "AVCC") (class "Default")
      (node (ref "C48") (pin "1") (pinfunction "1_1") (pintype "unspecified"))
      (node (ref "C50") (pin "1") (pinfunction "1_1") (pintype "unspecified"))
      (node (ref "CN4") (pin "1") (pinfunction "1_1") (pintype "input"))
      (node (ref "U2") (pin "28") (pinfunction "VREF+_28") (pintype "input"))
      (node (ref "U2") (pin "29") (pinfunction "VDDA_29") (pintype "input"))
      (node (ref "U4") (pin "5") (pinfunction "OUT_5") (pintype "input"))
    )
    (net (code "24") (name "DCBUS") (class "Default")
      (node (ref "C10") (pin "2") (pinfunction "2_2") (pintype "input"))
      (node (ref "C11") (pin "2") (pinfunction "2_2") (pintype "input"))
      (node (ref "C12") (pin "2") (pinfunction "2_2") (pintype "input"))
      (node (ref "C13") (pin "2") (pinfunction "2_2") (pintype "input"))
      (node (ref "C14") (pin "2") (pinfunction "2_2") (pintype "input"))
      (node (ref "C15") (pin "2") (pinfunction "2_2") (pintype "input"))
      (node (ref "C16") (pin "2") (pinfunction "2_2") (pintype "input"))
      (node (ref "C17") (pin "1") (pinfunction "1_1") (pintype "input"))
      (node (ref "C18") (pin "1") (pinfunction "1_1") (pintype "input"))
      (node (ref "C19") (pin "2") (pinfunction "2_2") (pintype "input"))
      (node (ref "C20") (pin "2") (pinfunction "2_2") (pintype "input"))
      (node (ref "C23") (pin "1") (pinfunction "1_1") (pintype "input"))
      (node (ref "C24") (pin "1") (pinfunction "1_1") (pintype "unspecified"))
      (node (ref "C36") (pin "2") (pinfunction "2_2") (pintype "input"))
      (node (ref "C43") (pin "2") (pinfunction "2_2") (pintype "input"))
      (node (ref "CN8") (pin "1") (pinfunction "1_1") (pintype "input"))
      (node (ref "Q12") (pin "4") (pinfunction "D_4") (pintype "unspecified"))
      (node (ref "R12") (pin "1") (pinfunction "1_1") (pintype "unspecified"))
      (node (ref "R15") (pin "2") (pinfunction "2_2") (pintype "unspecified"))
      (node (ref "R17") (pin "2") (pinfunction "2_2") (pintype "unspecified"))
      (node (ref "R20") (pin "1") (pinfunction "1_1") (pintype "unspecified"))
      (node (ref "R52") (pin "2") (pinfunction "2_2") (pintype "unspecified"))
      (node (ref "R60") (pin "2") (pinfunction "2_2") (pintype "input"))
      (node (ref "U6") (pin "2") (pinfunction "VIN_2") (pintype "input"))
    )
    (net (code "25") (name "GND") (class "Default")
      (node (ref "C1") (pin "2") (pinfunction "2_2") (pintype "unspecified"))
      (node (ref "C10") (pin "1") (pinfunction "1_1") (pintype "input"))
      (node (ref "C106") (pin "2") (pinfunction "2_2") (pintype "unspecified"))
      (node (ref "C11") (pin "1") (pinfunction "1_1") (pintype "input"))
      (node (ref "C12") (pin "1") (pinfunction "1_1") (pintype "input"))
      (node (ref "C13") (pin "1") (pinfunction "1_1") (pintype "input"))
      (node (ref "C14") (pin "1") (pinfunction "1_1") (pintype "input"))
      (node (ref "C15") (pin "1") (pinfunction "1_1") (pintype "input"))
      (node (ref "C16") (pin "1") (pinfunction "1_1") (pintype "input"))
      (node (ref "C17") (pin "2") (pinfunction "2_2") (pintype "input"))
      (node (ref "C18") (pin "2") (pinfunction "2_2") (pintype "input"))
      (node (ref "C19") (pin "1") (pinfunction "1_1") (pintype "input"))
      (node (ref "C20") (pin "1") (pinfunction "1_1") (pintype "input"))
      (node (ref "C23") (pin "2") (pinfunction "2_2") (pintype "input"))
      (node (ref "C24") (pin "2") (pinfunction "2_2") (pintype "unspecified"))
      (node (ref "C26") (pin "1") (pinfunction "1_1") (pintype "unspecified"))
      (node (ref "C27") (pin "2") (pinfunction "2_2") (pintype "input"))
      (node (ref "C28") (pin "2") (pinfunction "2_2") (pintype "input"))
      (node (ref "C29") (pin "2") (pinfunction "2_2") (pintype "input"))
      (node (ref "C30") (pin "2") (pinfunction "2_2") (pintype "unspecified"))
      (node (ref "C31") (pin "2") (pinfunction "2_2") (pintype "unspecified"))
      (node (ref "C32") (pin "2") (pinfunction "2_2") (pintype "unspecified"))
      (node (ref "C33") (pin "2") (pinfunction "2_2") (pintype "unspecified"))
      (node (ref "C34") (pin "2") (pinfunction "2_2") (pintype "input"))
      (node (ref "C35") (pin "2") (pinfunction "2_2") (pintype "input"))
      (node (ref "C36") (pin "1") (pinfunction "1_1") (pintype "input"))
      (node (ref "C37") (pin "1") (pinfunction "1_1") (pintype "input"))
      (node (ref "C38") (pin "2") (pinfunction "2_2") (pintype "input"))
      (node (ref "C39") (pin "1") (pinfunction "1_1") (pintype "input"))
      (node (ref "C43") (pin "1") (pinfunction "1_1") (pintype "input"))
      (node (ref "C44") (pin "2") (pinfunction "2_2") (pintype "unspecified"))
      (node (ref "C45") (pin "2") (pinfunction "2_2") (pintype "unspecified"))
      (node (ref "C46") (pin "2") (pinfunction "2_2") (pintype "unspecified"))
      (node (ref "C47") (pin "1") (pinfunction "1_1") (pintype "unspecified"))
      (node (ref "C51") (pin "2") (pinfunction "2_2") (pintype "unspecified"))
      (node (ref "C52") (pin "1") (pinfunction "1_1") (pintype "unspecified"))
      (node (ref "C55") (pin "2") (pinfunction "2_2") (pintype "unspecified"))
      (node (ref "C56") (pin "2") (pinfunction "2_2") (pintype "unspecified"))
      (node (ref "C57") (pin "2") (pinfunction "2_2") (pintype "unspecified"))
      (node (ref "C59") (pin "2") (pinfunction "2_2") (pintype "input"))
      (node (ref "C6") (pin "1") (pinfunction "1_1") (pintype "unspecified"))
      (node (ref "C61") (pin "2") (pinfunction "2_2") (pintype "unspecified"))
      (node (ref "C62") (pin "2") (pinfunction "2_2") (pintype "unspecified"))
      (node (ref "C63") (pin "1") (pinfunction "1_1") (pintype "unspecified"))
      (node (ref "C64") (pin "1") (pinfunction "1_1") (pintype "unspecified"))
      (node (ref "C65") (pin "2") (pinfunction "2_2") (pintype "unspecified"))
      (node (ref "C66") (pin "2") (pinfunction "2_2") (pintype "input"))
      (node (ref "C67") (pin "2") (pinfunction "2_2") (pintype "input"))
      (node (ref "C68") (pin "2") (pinfunction "2_2") (pintype "input"))
      (node (ref "C69") (pin "1") (pinfunction "1_1") (pintype "unspecified"))
      (node (ref "C75") (pin "2") (pinfunction "2_2") (pintype "unspecified"))
      (node (ref "C80") (pin "1") (pinfunction "1_1") (pintype "unspecified"))
      (node (ref "C81") (pin "1") (pinfunction "1_1") (pintype "unspecified"))
      (node (ref "C82") (pin "1") (pinfunction "1_1") (pintype "unspecified"))
      (node (ref "C83") (pin "1") (pinfunction "1_1") (pintype "unspecified"))
      (node (ref "C9") (pin "2") (pinfunction "2_2") (pintype "input"))
      (node (ref "CN1") (pin "1") (pinfunction "-_1") (pintype "unspecified"))
      (node (ref "CN10") (pin "1") (pinfunction "1_1") (pintype "unspecified"))
      (node (ref "CN10") (pin "3") (pinfunction "3_3") (pintype "unspecified"))
      (node (ref "CN10") (pin "4") (pinfunction "4_4") (pintype "unspecified"))
      (node (ref "CN6") (pin "1") (pinfunction "1_1") (pintype "input"))
      (node (ref "CN9") (pin "7") (pinfunction "7_7") (pintype "unspecified"))
      (node (ref "CN9") (pin "8") (pinfunction "8_8") (pintype "unspecified"))
      (node (ref "CN9") (pin "9") (pinfunction "9_9") (pintype "unspecified"))
      (node (ref "D1") (pin "1") (pinfunction "1_1") (pintype "unspecified"))
      (node (ref "D10") (pin "2") (pinfunction "A_2") (pintype "unspecified"))
      (node (ref "D11") (pin "1") (pinfunction "1_1") (pintype "unspecified"))
      (node (ref "D2") (pin "1") (pinfunction "1_1") (pintype "unspecified"))
      (node (ref "D3") (pin "1") (pinfunction "1_1") (pintype "unspecified"))
      (node (ref "D4") (pin "1") (pinfunction "1_1") (pintype "unspecified"))
      (node (ref "D5") (pin "2") (pinfunction "A_2") (pintype "unspecified"))
      (node (ref "D7") (pin "2") (pinfunction "A_2") (pintype "unspecified"))
      (node (ref "K1") (pin "1") (pinfunction "1_1") (pintype "input"))
      (node (ref "K2") (pin "1") (pinfunction "1_1") (pintype "input"))
      (node (ref "L1") (pin "2") (pinfunction "2_2") (pintype "input"))
      (node (ref "L10") (pin "2") (pinfunction "2_2") (pintype "input"))
      (node (ref "L3") (pin "2") (pinfunction "2_2") (pintype "input"))
      (node (ref "L4") (pin "2") (pinfunction "2_2") (pintype "input"))
      (node (ref "L5") (pin "2") (pinfunction "2_2") (pintype "input"))
      (node (ref "LED1") (pin "1") (pinfunction "GND_1") (pintype "input"))
      (node (ref "Q3") (pin "1") (pinfunction "S_1") (pintype "unspecified"))
      (node (ref "Q3") (pin "2") (pinfunction "S_2") (pintype "unspecified"))
      (node (ref "Q3") (pin "3") (pinfunction "S_3") (pintype "unspecified"))
      (node (ref "Q4") (pin "1") (pinfunction "S_1") (pintype "unspecified"))
      (node (ref "Q4") (pin "2") (pinfunction "S_2") (pintype "unspecified"))
      (node (ref "Q4") (pin "3") (pinfunction "S_3") (pintype "unspecified"))
      (node (ref "R10") (pin "1") (pinfunction "1_1") (pintype "input"))
      (node (ref "R21") (pin "1") (pinfunction "1_1") (pintype "input"))
      (node (ref "R28") (pin "1") (pinfunction "1_1") (pintype "unspecified"))
      (node (ref "R29") (pin "1") (pinfunction "1_1") (pintype "input"))
      (node (ref "R32") (pin "2") (pinfunction "2_2") (pintype "input"))
      (node (ref "R33") (pin "1") (pinfunction "1_1") (pintype "input"))
      (node (ref "R33") (pin "2") (pinfunction "2_2") (pintype "input"))
      (node (ref "R34") (pin "1") (pinfunction "1_1") (pintype "input"))
      (node (ref "R34") (pin "2") (pinfunction "2_2") (pintype "input"))
      (node (ref "R37") (pin "1") (pinfunction "1_1") (pintype "unspecified"))
      (node (ref "R39") (pin "2") (pinfunction "2_2") (pintype "input"))
      (node (ref "R53") (pin "2") (pinfunction "2_2") (pintype "input"))
      (node (ref "R61") (pin "1") (pinfunction "1_1") (pintype "input"))
      (node (ref "U1") (pin "21") (pinfunction "SYNC_21") (pintype "unspecified"))
      (node (ref "U1") (pin "23") (pinfunction "GND_23") (pintype "unspecified"))
      (node (ref "U1") (pin "28") (pinfunction "GND_28") (pintype "unspecified"))
      (node (ref "U1") (pin "29") (pinfunction "GND_29") (pintype "unspecified"))
      (node (ref "U2") (pin "15") (pinfunction "VSS_15") (pintype "input"))
      (node (ref "U2") (pin "31") (pinfunction "VSS_31") (pintype "input"))
      (node (ref "U2") (pin "47") (pinfunction "VSS_47") (pintype "input"))
      (node (ref "U2") (pin "63") (pinfunction "VSS_63") (pintype "input"))
      (node (ref "U3") (pin "2") (pinfunction "VSS_2") (pintype "input"))
      (node (ref "U4") (pin "2") (pinfunction "GND_2") (pintype "input"))
      (node (ref "U5") (pin "2") (pinfunction "GND_2") (pintype "input"))
      (node (ref "U6") (pin "1") (pinfunction "GND_1") (pintype "input"))
      (node (ref "U6") (pin "9") (pinfunction "EP_9") (pintype "input"))
      (node (ref "U8") (pin "4") (pinfunction "GND_4") (pintype "unspecified"))
      (node (ref "X1") (pin "2") (pinfunction "GND_2") (pintype "input"))
      (node (ref "X1") (pin "4") (pinfunction "GND_4") (pintype "input"))
    )
    (net (code "26") (name "GND_BAT") (class "Default")
      (node (ref "C3") (pin "1") (pinfunction "1_1") (pintype "input"))
      (node (ref "C4") (pin "1") (pinfunction "1_1") (pintype "input"))
      (node (ref "C5") (pin "2") (pinfunction "2_2") (pintype "input"))
      (node (ref "CN2") (pin "1") (pinfunction "-_1") (pintype "unspecified"))
      (node (ref "D6") (pin "1") (pinfunction "1_1") (pintype "unspecified"))
      (node (ref "Q4") (pin "5") (pinfunction "D_5") (pintype "unspecified"))
      (node (ref "U7") (pin "2") (pinfunction "A_2") (pintype "unspecified"))
    )
    (net (code "27") (name "Net-(C5-Pad1)") (class "Default")
      (node (ref "C5") (pin "1") (pinfunction "1_1") (pintype "input"))
      (node (ref "R6") (pin "1") (pinfunction "1_1") (pintype "unspecified"))
    )
    (net (code "28") (name "Net-(C9-Pad1)") (class "Default")
      (node (ref "C9") (pin "1") (pinfunction "1_1") (pintype "input"))
      (node (ref "R17") (pin "1") (pinfunction "1_1") (pintype "unspecified"))
    )
    (net (code "29") (name "Net-(C22-Pad1)") (class "Default")
      (node (ref "C22") (pin "1") (pinfunction "1_1") (pintype "input"))
      (node (ref "C25") (pin "1") (pinfunction "1_1") (pintype "input"))
      (node (ref "R13") (pin "1") (pinfunction "1_1") (pintype "unspecified"))
    )
    (net (code "30") (name "Net-(C42-Pad1)") (class "Default")
      (node (ref "C42") (pin "1") (pinfunction "1_1") (pintype "unspecified"))
      (node (ref "R4") (pin "2") (pinfunction "2_2") (pintype "unspecified"))
    )
    (net (code "31") (name "Net-(C69-Pad2)") (class "Default")
      (node (ref "C69") (pin "2") (pinfunction "2_2") (pintype "unspecified"))
      (node (ref "R48") (pin "1") (pinfunction "1_1") (pintype "unspecified"))
    )
    (net (code "32") (name "Net-(C106-Pad1)") (class "Default")
      (node (ref "C106") (pin "1") (pinfunction "1_1") (pintype "unspecified"))
      (node (ref "C44") (pin "1") (pinfunction "1_1") (pintype "unspecified"))
      (node (ref "C45") (pin "1") (pinfunction "1_1") (pintype "unspecified"))
      (node (ref "C46") (pin "1") (pinfunction "1_1") (pintype "unspecified"))
      (node (ref "L7") (pin "2") (pinfunction "2_2") (pintype "input"))
      (node (ref "R27") (pin "1") (pinfunction "1_1") (pintype "input"))
      (node (ref "R36") (pin "1") (pinfunction "1_1") (pintype "input"))
    )
    (net (code "33") (name "Net-(CN9-Pad2)") (class "Default")
      (node (ref "CN9") (pin "2") (pinfunction "2_2") (pintype "unspecified"))
      (node (ref "D2") (pin "2") (pinfunction "2_2") (pintype "unspecified"))
      (node (ref "R66") (pin "2") (pinfunction "2_2") (pintype "unspecified"))
    )
    (net (code "34") (name "Net-(CN9-Pad3)") (class "Default")
      (node (ref "CN9") (pin "3") (pinfunction "3_3") (pintype "unspecified"))
      (node (ref "D1") (pin "2") (pinfunction "2_2") (pintype "unspecified"))
      (node (ref "R65") (pin "2") (pinfunction "2_2") (pintype "unspecified"))
    )
    (net (code "35") (name "Net-(CN9-Pad4)") (class "Default")
      (node (ref "CN9") (pin "4") (pinfunction "4_4") (pintype "unspecified"))
      (node (ref "D3") (pin "2") (pinfunction "2_2") (pintype "unspecified"))
      (node (ref "R64") (pin "2") (pinfunction "2_2") (pintype "unspecified"))
    )
    (net (code "36") (name "Net-(CN9-Pad5)") (class "Default")
      (node (ref "CN9") (pin "5") (pinfunction "5_5") (pintype "unspecified"))
      (node (ref "D4") (pin "2") (pinfunction "2_2") (pintype "unspecified"))
      (node (ref "R50") (pin "2") (pinfunction "2_2") (pintype "unspecified"))
    )
    (net (code "37") (name "Net-(CN9-Pad6)") (class "Default")
      (node (ref "CN9") (pin "6") (pinfunction "6_6") (pintype "unspecified"))
      (node (ref "D11") (pin "2") (pinfunction "2_2") (pintype "unspecified"))
      (node (ref "R44") (pin "2") (pinfunction "2_2") (pintype "unspecified"))
    )
    (net (code "38") (name "Net-(D5-K)") (class "Default")
      (node (ref "C76") (pin "2") (pinfunction "2_2") (pintype "input"))
      (node (ref "D5") (pin "1") (pinfunction "K_1") (pintype "unspecified"))
      (node (ref "L6") (pin "1") (pinfunction "1_1") (pintype "unspecified"))
      (node (ref "Q1") (pin "1") (pinfunction "S_1") (pintype "unspecified"))
      (node (ref "Q1") (pin "2") (pinfunction "S_2") (pintype "unspecified"))
      (node (ref "Q1") (pin "3") (pinfunction "S_3") (pintype "unspecified"))
      (node (ref "Q3") (pin "5") (pinfunction "D_5") (pintype "unspecified"))
      (node (ref "Q3") (pin "6") (pinfunction "D_6") (pintype "unspecified"))
      (node (ref "Q3") (pin "7") (pinfunction "D_7") (pintype "unspecified"))
      (node (ref "Q3") (pin "8") (pinfunction "D_8") (pintype "unspecified"))
      (node (ref "Q3") (pin "9") (pinfunction "D_9") (pintype "unspecified"))
      (node (ref "R48") (pin "2") (pinfunction "2_2") (pintype "unspecified"))
      (node (ref "R5") (pin "1") (pinfunction "1_1") (pintype "input"))
      (node (ref "U1") (pin "26") (pinfunction "SW_26") (pintype "unspecified"))
    )
    (net (code "39") (name "Net-(D7-K)") (class "Default")
      (node (ref "C6") (pin "2") (pinfunction "2_2") (pintype "unspecified"))
      (node (ref "D7") (pin "1") (pinfunction "K_1") (pintype "unspecified"))
      (node (ref "Q4") (pin "4") (pinfunction "G_4") (pintype "unspecified"))
      (node (ref "R7") (pin "1") (pinfunction "1_1") (pintype "unspecified"))
    )
    (net (code "40") (name "Net-(D8-A)") (class "Default")
      (node (ref "C8") (pin "1") (pinfunction "1_1") (pintype "unspecified"))
      (node (ref "D8") (pin "2") (pinfunction "A_2") (pintype "unspecified"))
      (node (ref "Q12") (pin "1") (pinfunction "G_1") (pintype "unspecified"))
      (node (ref "R11") (pin "1") (pinfunction "1_1") (pintype "input"))
    )
    (net (code "41") (name "Net-(D9-A)") (class "Default")
      (node (ref "C75") (pin "1") (pinfunction "1_1") (pintype "unspecified"))
      (node (ref "CN15") (pin "1") (pinfunction "1_1") (pintype "input"))
      (node (ref "D9") (pin "2") (pinfunction "A_2") (pintype "unspecified"))
      (node (ref "U1") (pin "2") (pinfunction "INTVCC_2") (pintype "unspecified"))
    )
    (net (code "42") (name "Net-(D9-K)") (class "Default")
      (node (ref "C76") (pin "1") (pinfunction "1_1") (pintype "input"))
      (node (ref "D9") (pin "1") (pinfunction "K_1") (pintype "unspecified"))
      (node (ref "U1") (pin "27") (pinfunction "BOOST_27") (pintype "unspecified"))
    )
    (net (code "43") (name "Net-(D12-A)") (class "Default")
      (node (ref "D12") (pin "2") (pinfunction "A_2") (pintype "unspecified"))
      (node (ref "Q3") (pin "4") (pinfunction "G_4") (pintype "unspecified"))
      (node (ref "R32") (pin "1") (pinfunction "1_1") (pintype "input"))
      (node (ref "R71") (pin "1") (pinfunction "1_1") (pintype "unspecified"))
    )
    (net (code "44") (name "Net-(D12-C)") (class "Default")
      (node (ref "D12") (pin "1") (pinfunction "C_1") (pintype "unspecified"))
      (node (ref "R71") (pin "2") (pinfunction "2_2") (pintype "unspecified"))
      (node (ref "U1") (pin "1") (pinfunction "BG_1") (pintype "unspecified"))
    )
    (net (code "45") (name "Net-(L1-Pad1)") (class "Default")
      (node (ref "L1") (pin "1") (pinfunction "1_1") (pintype "input"))
      (node (ref "R20") (pin "2") (pinfunction "2_2") (pintype "unspecified"))
    )
    (net (code "46") (name "Net-(L3-Pad1)") (class "Default")
      (node (ref "L3") (pin "1") (pinfunction "1_1") (pintype "input"))
      (node (ref "R14") (pin "1") (pinfunction "1_1") (pintype "input"))
    )
    (net (code "47") (name "Net-(L4-Pad1)") (class "Default")
      (node (ref "L4") (pin "1") (pinfunction "1_1") (pintype "input"))
      (node (ref "R25") (pin "2") (pinfunction "2_2") (pintype "input"))
    )
    (net (code "48") (name "Net-(L5-Pad1)") (class "Default")
      (node (ref "L5") (pin "1") (pinfunction "1_1") (pintype "input"))
      (node (ref "R26") (pin "2") (pinfunction "2_2") (pintype "input"))
    )
    (net (code "49") (name "Net-(L6-Pad2)") (class "Default")
      (node (ref "L6") (pin "2") (pinfunction "2_2") (pintype "unspecified"))
      (node (ref "R1") (pin "1") (pinfunction "1_1") (pintype "unspecified"))
      (node (ref "R23") (pin "2") (pinfunction "2_2") (pintype "input"))
    )
    (net (code "50") (name "Net-(L10-Pad1)") (class "Default")
      (node (ref "L10") (pin "1") (pinfunction "1_1") (pintype "input"))
      (node (ref "R45") (pin "2") (pinfunction "2_2") (pintype "input"))
    )
    (net (code "51") (name "Net-(Q1-G)") (class "Default")
      (node (ref "Q1") (pin "4") (pinfunction "G_4") (pintype "unspecified"))
      (node (ref "R5") (pin "2") (pinfunction "2_2") (pintype "input"))
      (node (ref "R70") (pin "1") (pinfunction "1_1") (pintype "unspecified"))
    )
    (net (code "52") (name "Net-(Q11-B)") (class "Default")
      (node (ref "C7") (pin "2") (pinfunction "2_2") (pintype "unspecified"))
      (node (ref "Q11") (pin "1") (pinfunction "B_1") (pintype "unspecified"))
      (node (ref "R9") (pin "1") (pinfunction "1_1") (pintype "input"))
    )
    (net (code "53") (name "Net-(Q11-C)") (class "Default")
      (node (ref "C7") (pin "1") (pinfunction "1_1") (pintype "unspecified"))
      (node (ref "Q11") (pin "3") (pinfunction "C_3") (pintype "unspecified"))
      (node (ref "R10") (pin "2") (pinfunction "2_2") (pintype "input"))
      (node (ref "R11") (pin "2") (pinfunction "2_2") (pintype "input"))
    )
    (net (code "54") (name "Net-(U1-CTRL2)") (class "Default")
      (node (ref "C54") (pin "2") (pinfunction "2_2") (pintype "unspecified"))
      (node (ref "R56") (pin "1") (pinfunction "1_1") (pintype "unspecified"))
      (node (ref "R57") (pin "2") (pinfunction "2_2") (pintype "input"))
      (node (ref "U1") (pin "13") (pinfunction "CTRL2_13") (pintype "unspecified"))
    )
    (net (code "55") (name "Net-(U1-EN{slash}UVLO)") (class "Default")
      (node (ref "C52") (pin "2") (pinfunction "2_2") (pintype "unspecified"))
      (node (ref "R52") (pin "1") (pinfunction "1_1") (pintype "unspecified"))
      (node (ref "R53") (pin "1") (pinfunction "1_1") (pintype "input"))
      (node (ref "U1") (pin "4") (pinfunction "EN/UVLO_4") (pintype "unspecified"))
    )
    (net (code "56") (name "Net-(U1-FB)") (class "Default")
      (node (ref "R30") (pin "1") (pinfunction "1_1") (pintype "unspecified"))
      (node (ref "R49") (pin "1") (pinfunction "1_1") (pintype "input"))
      (node (ref "U1") (pin "11") (pinfunction "FB_11") (pintype "unspecified"))
    )
    (net (code "57") (name "Net-(U1-FBIN)") (class "Default")
      (node (ref "C2") (pin "1") (pinfunction "1_1") (pintype "unspecified"))
      (node (ref "CN16") (pin "1") (pinfunction "1_1") (pintype "input"))
      (node (ref "R57") (pin "1") (pinfunction "1_1") (pintype "input"))
      (node (ref "U1") (pin "10") (pinfunction "FBIN_10") (pintype "unspecified"))
      (node (ref "U1") (pin "5") (pinfunction "VREF_5") (pintype "unspecified"))
    )
    (net (code "58") (name "Net-(U1-ISMON)") (class "Default")
      (node (ref "CN12") (pin "1") (pinfunction "1_1") (pintype "input"))
      (node (ref "R63") (pin "2") (pinfunction "2_2") (pintype "input"))
      (node (ref "U1") (pin "19") (pinfunction "ISMON_19") (pintype "unspecified"))
    )
    (net (code "59") (name "Net-(U1-IVINMON)") (class "Default")
      (node (ref "CN17") (pin "1") (pinfunction "1_1") (pintype "input"))
      (node (ref "R62") (pin "2") (pinfunction "2_2") (pintype "input"))
      (node (ref "U1") (pin "8") (pinfunction "IVINMON_8") (pintype "unspecified"))
    )
    (net (code "60") (name "Net-(U1-IVINN)") (class "Default")
      (node (ref "C77") (pin "2") (pinfunction "2_2") (pintype "unspecified"))
      (node (ref "R59") (pin "1") (pinfunction "1_1") (pintype "input"))
      (node (ref "U1") (pin "6") (pinfunction "IVINN_6") (pintype "unspecified"))
    )
    (net (code "61") (name "Net-(U1-IVINP)") (class "Default")
      (node (ref "C77") (pin "1") (pinfunction "1_1") (pintype "unspecified"))
      (node (ref "R60") (pin "1") (pinfunction "1_1") (pintype "input"))
      (node (ref "U1") (pin "7") (pinfunction "IVINP_7") (pintype "unspecified"))
    )
    (net (code "62") (name "Net-(U1-PWM)") (class "Default")
      (node (ref "C60") (pin "2") (pinfunction "2_2") (pintype "unspecified"))
      (node (ref "R40") (pin "2") (pinfunction "2_2") (pintype "input"))
      (node (ref "R41") (pin "1") (pinfunction "1_1") (pintype "input"))
      (node (ref "U1") (pin "22") (pinfunction "PWM_22") (pintype "unspecified"))
    )
    (net (code "63") (name "Net-(U1-RT)") (class "Default")
      (node (ref "R22") (pin "2") (pinfunction "2_2") (pintype "unspecified"))
      (node (ref "U1") (pin "20") (pinfunction "RT_20") (pintype "unspecified"))
    )
    (net (code "64") (name "Net-(U1-SENSE+)") (class "Default")
      (node (ref "C49") (pin "2") (pinfunction "2_2") (pintype "unspecified"))
      (node (ref "R23") (pin "1") (pinfunction "1_1") (pintype "input"))
      (node (ref "U1") (pin "17") (pinfunction "SENSE+_17") (pintype "unspecified"))
    )
    (net (code "65") (name "Net-(U1-SENSE–)") (class "Default")
      (node (ref "C49") (pin "1") (pinfunction "1_1") (pintype "unspecified"))
      (node (ref "R24") (pin "1") (pinfunction "1_1") (pintype "input"))
      (node (ref "U1") (pin "16") (pinfunction "SENSE–_16") (pintype "unspecified"))
    )
    (net (code "66") (name "Net-(U1-SS)") (class "Default")
      (node (ref "C72") (pin "2") (pinfunction "2_2") (pintype "unspecified"))
      (node (ref "U1") (pin "15") (pinfunction "SS_15") (pintype "unspecified"))
    )
    (net (code "67") (name "Net-(U1-TG)") (class "Default")
      (node (ref "R70") (pin "2") (pinfunction "2_2") (pintype "unspecified"))
      (node (ref "U1") (pin "25") (pinfunction "TG_25") (pintype "unspecified"))
    )
    (net (code "68") (name "Net-(U1-VC)") (class "Default")
      (node (ref "R4") (pin "1") (pinfunction "1_1") (pintype "unspecified"))
      (node (ref "U1") (pin "18") (pinfunction "VC_18") (pintype "unspecified"))
    )
    (net (code "69") (name "Net-(U1-VIN)") (class "Default")
      (node (ref "C47") (pin "2") (pinfunction "2_2") (pintype "unspecified"))
      (node (ref "C80") (pin "2") (pinfunction "2_2") (pintype "unspecified"))
      (node (ref "C81") (pin "2") (pinfunction "2_2") (pintype "unspecified"))
      (node (ref "C82") (pin "2") (pinfunction "2_2") (pintype "unspecified"))
      (node (ref "C83") (pin "2") (pinfunction "2_2") (pintype "unspecified"))
      (node (ref "Q1") (pin "5") (pinfunction "D_5") (pintype "unspecified"))
      (node (ref "Q1") (pin "6") (pinfunction "D_6") (pintype "unspecified"))
      (node (ref "Q1") (pin "7") (pinfunction "D_7") (pintype "unspecified"))
      (node (ref "Q1") (pin "8") (pinfunction "D_8") (pintype "unspecified"))
      (node (ref "Q1") (pin "9") (pinfunction "D_9") (pintype "unspecified"))
      (node (ref "R12") (pin "2") (pinfunction "2_2") (pintype "unspecified"))
      (node (ref "R59") (pin "2") (pinfunction "2_2") (pintype "input"))
      (node (ref "U1") (pin "3") (pinfunction "VIN_3") (pintype "unspecified"))
    )
    (net (code "70") (name "Net-(U2-PA4)") (class "Default")
      (node (ref "R2") (pin "1") (pinfunction "1_1") (pintype "input"))
      (node (ref "U2") (pin "18") (pinfunction "PA4_18") (pintype "input"))
    )
    (net (code "71") (name "Net-(U2-PA8)") (class "Default")
      (node (ref "R55") (pin "1") (pinfunction "1_1") (pintype "input"))
      (node (ref "U2") (pin "42") (pinfunction "PA8_42") (pintype "input"))
    )
    (net (code "72") (name "Net-(U2-PA9)") (class "Default")
      (node (ref "R35") (pin "1") (pinfunction "1_1") (pintype "unspecified"))
      (node (ref "U2") (pin "43") (pinfunction "PA9_43") (pintype "input"))
    )
    (net (code "73") (name "Net-(U2-PB8-BOOT0)") (class "Default")
      (node (ref "R61") (pin "2") (pinfunction "2_2") (pintype "input"))
      (node (ref "U2") (pin "61") (pinfunction "PB8-BOOT0_61") (pintype "input"))
    )
    (net (code "74") (name "Net-(U2-PB12)") (class "Default")
      (node (ref "R54") (pin "1") (pinfunction "1_1") (pintype "unspecified"))
      (node (ref "U2") (pin "34") (pinfunction "PB12_34") (pintype "input"))
    )
    (net (code "75") (name "Net-(U5-BST)") (class "Default")
      (node (ref "C40") (pin "1") (pinfunction "1_1") (pintype "unspecified"))
      (node (ref "U5") (pin "1") (pinfunction "BST_1") (pintype "input"))
    )
    (net (code "76") (name "Net-(U5-EN)") (class "Default")
      (node (ref "R38") (pin "2") (pinfunction "2_2") (pintype "input"))
      (node (ref "U5") (pin "4") (pinfunction "EN_4") (pintype "input"))
    )
    (net (code "77") (name "Net-(U5-FB)") (class "Default")
      (node (ref "R36") (pin "2") (pinfunction "2_2") (pintype "input"))
      (node (ref "R39") (pin "1") (pinfunction "1_1") (pintype "input"))
      (node (ref "U5") (pin "3") (pinfunction "FB_3") (pintype "input"))
    )
    (net (code "78") (name "Net-(U5-SW)") (class "Default")
      (node (ref "C40") (pin "2") (pinfunction "2_2") (pintype "unspecified"))
      (node (ref "L7") (pin "1") (pinfunction "1_1") (pintype "input"))
      (node (ref "U5") (pin "6") (pinfunction "SW_6") (pintype "input"))
    )
    (net (code "79") (name "Net-(U6-BST)") (class "Default")
      (node (ref "C21") (pin "2") (pinfunction "2_2") (pintype "input"))
      (node (ref "U6") (pin "7") (pinfunction "BST_7") (pintype "input"))
    )
    (net (code "80") (name "Net-(U6-EN)") (class "Default")
      (node (ref "R15") (pin "1") (pinfunction "1_1") (pintype "unspecified"))
      (node (ref "U6") (pin "3") (pinfunction "EN_3") (pintype "input"))
    )
    (net (code "81") (name "Net-(U6-RON)") (class "Default")
      (node (ref "R28") (pin "2") (pinfunction "2_2") (pintype "unspecified"))
      (node (ref "U6") (pin "4") (pinfunction "RON_4") (pintype "input"))
    )
    (net (code "82") (name "Net-(U6-SW)") (class "Default")
      (node (ref "C21") (pin "1") (pinfunction "1_1") (pintype "input"))
      (node (ref "L2") (pin "1") (pinfunction "1_1") (pintype "unspecified"))
      (node (ref "R13") (pin "2") (pinfunction "2_2") (pintype "unspecified"))
      (node (ref "U6") (pin "8") (pinfunction "SW_8") (pintype "input"))
    )
    (net (code "83") (name "Net-(U7-K)") (class "Default")
      (node (ref "R8") (pin "1") (pinfunction "1_1") (pintype "unspecified"))
      (node (ref "R9") (pin "2") (pinfunction "2_2") (pintype "input"))
      (node (ref "U7") (pin "1") (pinfunction "K_1") (pintype "unspecified"))
    )
    (net (code "84") (name "Net-(U8-Anode)") (class "Default")
      (node (ref "R18") (pin "2") (pinfunction "2_2") (pintype "input"))
      (node (ref "U8") (pin "1") (pinfunction "Anode_1") (pintype "unspecified"))
    )
    (net (code "85") (name "VCC") (class "Default")
      (node (ref "C31") (pin "1") (pinfunction "1_1") (pintype "unspecified"))
      (node (ref "C32") (pin "1") (pinfunction "1_1") (pintype "unspecified"))
      (node (ref "C33") (pin "1") (pinfunction "1_1") (pintype "unspecified"))
      (node (ref "C55") (pin "1") (pinfunction "1_1") (pintype "unspecified"))
      (node (ref "C56") (pin "1") (pinfunction "1_1") (pintype "unspecified"))
      (node (ref "C57") (pin "1") (pinfunction "1_1") (pintype "unspecified"))
      (node (ref "C62") (pin "1") (pinfunction "1_1") (pintype "unspecified"))
      (node (ref "CN5") (pin "1") (pinfunction "1_1") (pintype "input"))
      (node (ref "CN9") (pin "1") (pinfunction "1_1") (pintype "unspecified"))
      (node (ref "R14") (pin "2") (pinfunction "2_2") (pintype "input"))
      (node (ref "R3") (pin "2") (pinfunction "2_2") (pintype "input"))
      (node (ref "R31") (pin "1") (pinfunction "1_1") (pintype "input"))
      (node (ref "R67") (pin "1") (pinfunction "1_1") (pintype "input"))
      (node (ref "U2") (pin "1") (pinfunction "VBAT_1") (pintype "input"))
      (node (ref "U2") (pin "16") (pinfunction "VDD_16") (pintype "input"))
      (node (ref "U2") (pin "32") (pinfunction "VDD_32") (pintype "input"))
      (node (ref "U2") (pin "48") (pinfunction "VDD_48") (pintype "input"))
      (node (ref "U2") (pin "64") (pinfunction "VDD_64") (pintype "input"))
      (node (ref "U3") (pin "5") (pinfunction "VOUT_5") (pintype "input"))
      (node (ref "U8") (pin "6") (pinfunction "VDD_6") (pintype "unspecified"))
    )
    (net (code "86") (name "VCC_BAT") (class "Default")
      (node (ref "C3") (pin "2") (pinfunction "2_2") (pintype "input"))
      (node (ref "C4") (pin "2") (pinfunction "2_2") (pintype "input"))
      (node (ref "C8") (pin "2") (pinfunction "2_2") (pintype "unspecified"))
      (node (ref "CN2") (pin "2") (pinfunction "+_2") (pintype "unspecified"))
      (node (ref "CN3") (pin "1") (pinfunction "1_1") (pintype "input"))
      (node (ref "D6") (pin "2") (pinfunction "2_2") (pintype "unspecified"))
      (node (ref "D8") (pin "1") (pinfunction "K_1") (pintype "unspecified"))
      (node (ref "Q11") (pin "2") (pinfunction "E_2") (pintype "unspecified"))
      (node (ref "Q12") (pin "3") (pinfunction "S_3") (pintype "unspecified"))
      (node (ref "R6") (pin "2") (pinfunction "2_2") (pintype "unspecified"))
      (node (ref "R7") (pin "2") (pinfunction "2_2") (pintype "unspecified"))
      (node (ref "R8") (pin "2") (pinfunction "2_2") (pintype "unspecified"))
    )
    (net (code "87") (name "VCC_OUT") (class "Default")
      (node (ref "C59") (pin "1") (pinfunction "1_1") (pintype "input"))
      (node (ref "C63") (pin "2") (pinfunction "2_2") (pintype "unspecified"))
      (node (ref "C64") (pin "2") (pinfunction "2_2") (pintype "unspecified"))
      (node (ref "CN1") (pin "2") (pinfunction "+_2") (pintype "unspecified"))
      (node (ref "CN14") (pin "1") (pinfunction "1_1") (pintype "input"))
      (node (ref "D10") (pin "1") (pinfunction "K_1") (pintype "unspecified"))
      (node (ref "R1") (pin "2") (pinfunction "2_2") (pintype "unspecified"))
      (node (ref "R24") (pin "2") (pinfunction "2_2") (pintype "input"))
      (node (ref "R30") (pin "2") (pinfunction "2_2") (pintype "unspecified"))
      (node (ref "R37") (pin "2") (pinfunction "2_2") (pintype "unspecified"))
    )
    (net (code "88") (name "unconnected-(CN1-Pad3)") (class "Default")
      (node (ref "CN1") (pin "3") (pinfunction "3_3") (pintype "unspecified+no_connect"))
    )
    (net (code "89") (name "unconnected-(CN1-Pad4)") (class "Default")
      (node (ref "CN1") (pin "4") (pinfunction "4_4") (pintype "unspecified+no_connect"))
    )
    (net (code "90") (name "unconnected-(CN2-Pad3)") (class "Default")
      (node (ref "CN2") (pin "3") (pinfunction "3_3") (pintype "unspecified"))
    )
    (net (code "91") (name "unconnected-(CN2-Pad4)") (class "Default")
      (node (ref "CN2") (pin "4") (pinfunction "4_4") (pintype "unspecified"))
    )
    (net (code "92") (name "unconnected-(L6-NC-Pad3)") (class "Default")
      (node (ref "L6") (pin "3") (pinfunction "NC_3") (pintype "unspecified+no_connect"))
    )
    (net (code "93") (name "unconnected-(LED1-DO-Pad4)") (class "Default")
      (node (ref "LED1") (pin "4") (pinfunction "DO_4") (pintype "input+no_connect"))
    )
    (net (code "94") (name "unconnected-(U1-PWM_OUT-Pad24)") (class "Default")
      (node (ref "U1") (pin "24") (pinfunction "PWM_OUT_24") (pintype "unspecified+no_connect"))
    )
    (net (code "95") (name "unconnected-(U2-PA0-Pad12)") (class "Default")
      (node (ref "U2") (pin "12") (pinfunction "PA0_12") (pintype "input"))
    )
    (net (code "96") (name "unconnected-(U2-PA1-Pad13)") (class "Default")
      (node (ref "U2") (pin "13") (pinfunction "PA1_13") (pintype "input"))
    )
    (net (code "97") (name "unconnected-(U2-PA2-Pad14)") (class "Default")
      (node (ref "U2") (pin "14") (pinfunction "PA2_14") (pintype "input"))
    )
    (net (code "98") (name "unconnected-(U2-PA3-Pad17)") (class "Default")
      (node (ref "U2") (pin "17") (pinfunction "PA3_17") (pintype "input"))
    )
    (net (code "99") (name "unconnected-(U2-PA6-Pad20)") (class "Default")
      (node (ref "U2") (pin "20") (pinfunction "PA6_20") (pintype "input"))
    )
    (net (code "100") (name "unconnected-(U2-PA7-Pad21)") (class "Default")
      (node (ref "U2") (pin "21") (pinfunction "PA7_21") (pintype "input"))
    )
    (net (code "101") (name "unconnected-(U2-PA10-Pad44)") (class "Default")
      (node (ref "U2") (pin "44") (pinfunction "PA10_44") (pintype "input"))
    )
    (net (code "102") (name "unconnected-(U2-PA11-Pad45)") (class "Default")
      (node (ref "U2") (pin "45") (pinfunction "PA11_45") (pintype "input"))
    )
    (net (code "103") (name "unconnected-(U2-PA12-Pad46)") (class "Default")
      (node (ref "U2") (pin "46") (pinfunction "PA12_46") (pintype "input"))
    )
    (net (code "104") (name "unconnected-(U2-PA15-Pad51)") (class "Default")
      (node (ref "U2") (pin "51") (pinfunction "PA15_51") (pintype "input"))
    )
    (net (code "105") (name "unconnected-(U2-PB0-Pad24)") (class "Default")
      (node (ref "U2") (pin "24") (pinfunction "PB0_24") (pintype "input"))
    )
    (net (code "106") (name "unconnected-(U2-PB1-Pad25)") (class "Default")
      (node (ref "U2") (pin "25") (pinfunction "PB1_25") (pintype "input"))
    )
    (net (code "107") (name "unconnected-(U2-PB2-Pad26)") (class "Default")
      (node (ref "U2") (pin "26") (pinfunction "PB2_26") (pintype "input"))
    )
    (net (code "108") (name "unconnected-(U2-PB3-Pad56)") (class "Default")
      (node (ref "U2") (pin "56") (pinfunction "PB3_56") (pintype "input"))
    )
    (net (code "109") (name "unconnected-(U2-PB4-Pad57)") (class "Default")
      (node (ref "U2") (pin "57") (pinfunction "PB4_57") (pintype "input"))
    )
    (net (code "110") (name "unconnected-(U2-PB5-Pad58)") (class "Default")
      (node (ref "U2") (pin "58") (pinfunction "PB5_58") (pintype "input"))
    )
    (net (code "111") (name "unconnected-(U2-PB6-Pad59)") (class "Default")
      (node (ref "U2") (pin "59") (pinfunction "PB6_59") (pintype "input"))
    )
    (net (code "112") (name "unconnected-(U2-PB7-Pad60)") (class "Default")
      (node (ref "U2") (pin "60") (pinfunction "PB7_60") (pintype "input"))
    )
    (net (code "113") (name "unconnected-(U2-PB9-Pad62)") (class "Default")
      (node (ref "U2") (pin "62") (pinfunction "PB9_62") (pintype "input"))
    )
    (net (code "114") (name "unconnected-(U2-PB13-Pad35)") (class "Default")
      (node (ref "U2") (pin "35") (pinfunction "PB13_35") (pintype "input"))
    )
    (net (code "115") (name "unconnected-(U2-PC0-Pad8)") (class "Default")
      (node (ref "U2") (pin "8") (pinfunction "PC0_8") (pintype "input"))
    )
    (net (code "116") (name "unconnected-(U2-PC1-Pad9)") (class "Default")
      (node (ref "U2") (pin "9") (pinfunction "PC1_9") (pintype "input"))
    )
    (net (code "117") (name "unconnected-(U2-PC2-Pad10)") (class "Default")
      (node (ref "U2") (pin "10") (pinfunction "PC2_10") (pintype "input"))
    )
    (net (code "118") (name "unconnected-(U2-PC3-Pad11)") (class "Default")
      (node (ref "U2") (pin "11") (pinfunction "PC3_11") (pintype "input"))
    )
    (net (code "119") (name "unconnected-(U2-PC4-Pad22)") (class "Default")
      (node (ref "U2") (pin "22") (pinfunction "PC4_22") (pintype "input"))
    )
    (net (code "120") (name "unconnected-(U2-PC5-Pad23)") (class "Default")
      (node (ref "U2") (pin "23") (pinfunction "PC5_23") (pintype "input"))
    )
    (net (code "121") (name "unconnected-(U2-PC6-Pad38)") (class "Default")
      (node (ref "U2") (pin "38") (pinfunction "PC6_38") (pintype "input"))
    )
    (net (code "122") (name "unconnected-(U2-PC7-Pad39)") (class "Default")
      (node (ref "U2") (pin "39") (pinfunction "PC7_39") (pintype "input"))
    )
    (net (code "123") (name "unconnected-(U2-PC8-Pad40)") (class "Default")
      (node (ref "U2") (pin "40") (pinfunction "PC8_40") (pintype "input"))
    )
    (net (code "124") (name "unconnected-(U2-PC10-Pad52)") (class "Default")
      (node (ref "U2") (pin "52") (pinfunction "PC10_52") (pintype "input"))
    )
    (net (code "125") (name "unconnected-(U2-PC11-Pad53)") (class "Default")
      (node (ref "U2") (pin "53") (pinfunction "PC11_53") (pintype "input"))
    )
    (net (code "126") (name "unconnected-(U2-PC12-Pad54)") (class "Default")
      (node (ref "U2") (pin "54") (pinfunction "PC12_54") (pintype "input"))
    )
    (net (code "127") (name "unconnected-(U2-PC14-OSC32_IN-Pad3)") (class "Default")
      (node (ref "U2") (pin "3") (pinfunction "PC14-OSC32_IN_3") (pintype "input"))
    )
    (net (code "128") (name "unconnected-(U2-PC15-OSC32_OUT-Pad4)") (class "Default")
      (node (ref "U2") (pin "4") (pinfunction "PC15-OSC32_OUT_4") (pintype "input"))
    )
    (net (code "129") (name "unconnected-(U2-PD2-Pad55)") (class "Default")
      (node (ref "U2") (pin "55") (pinfunction "PD2_55") (pintype "input"))
    )
    (net (code "130") (name "unconnected-(U3-NC-Pad4)") (class "Default")
      (node (ref "U3") (pin "4") (pinfunction "NC_4") (pintype "input"))
    )
    (net (code "131") (name "unconnected-(U4-NC-Pad4)") (class "Default")
      (node (ref "U4") (pin "4") (pinfunction "NC_4") (pintype "input"))
    )
    (net (code "132") (name "unconnected-(U6-PG-Pad6)") (class "Default")
      (node (ref "U6") (pin "6") (pinfunction "PG_6") (pintype "input"))
    )
    (net (code "133") (name "unconnected-(U8-N.C.-Pad2)") (class "Default")
      (node (ref "U8") (pin "2") (pinfunction "N.C._2") (pintype "unspecified"))
    )
  )
)
